# Nixie_Clock_v1_0.net
KiCad netlist of a schematic drawn in EAGLE
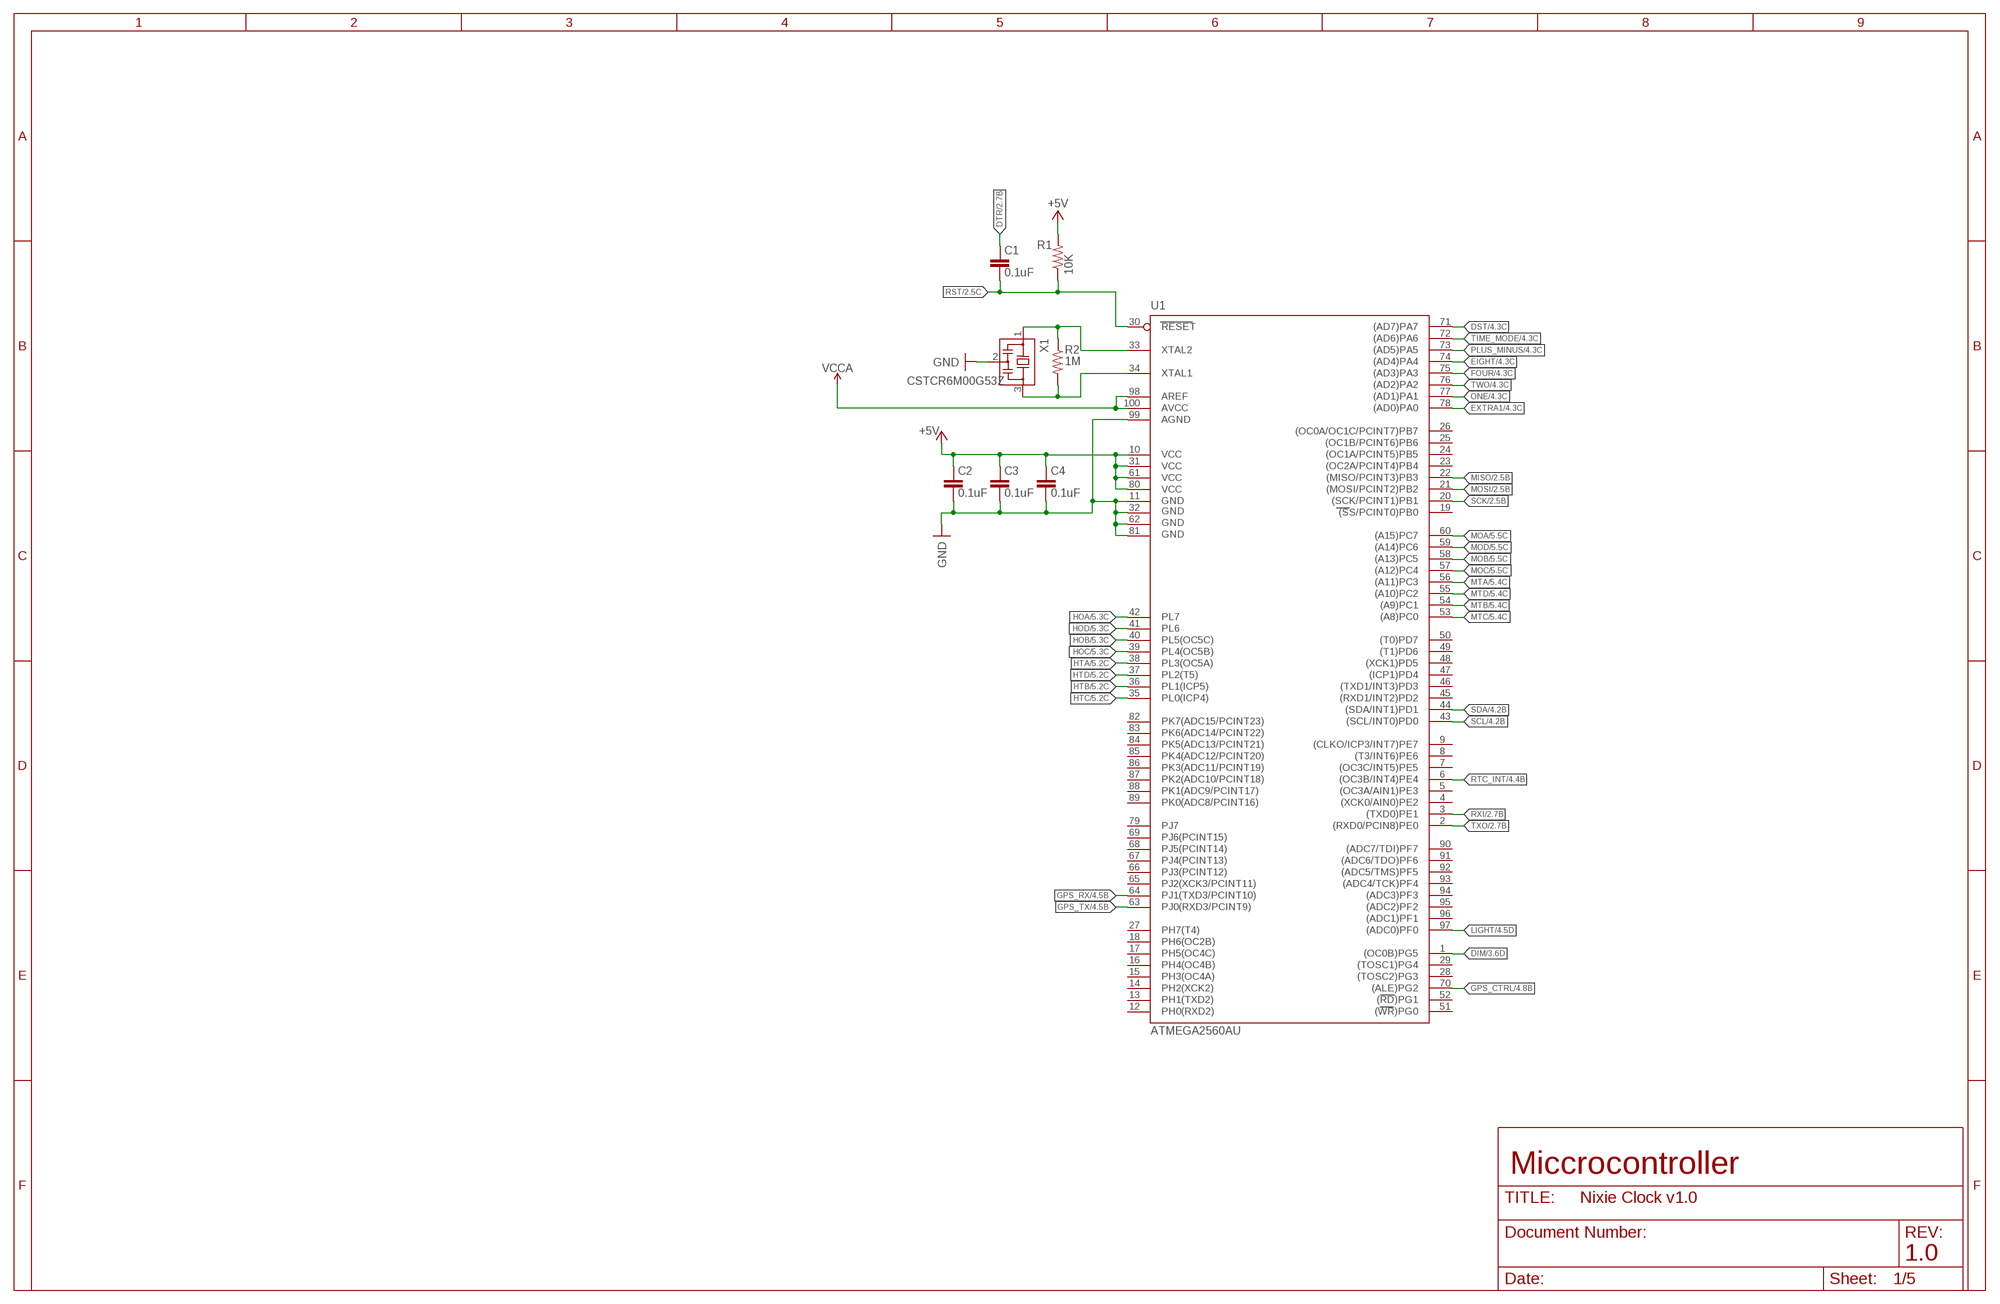
[diagram p0: schematic, sheet 1]
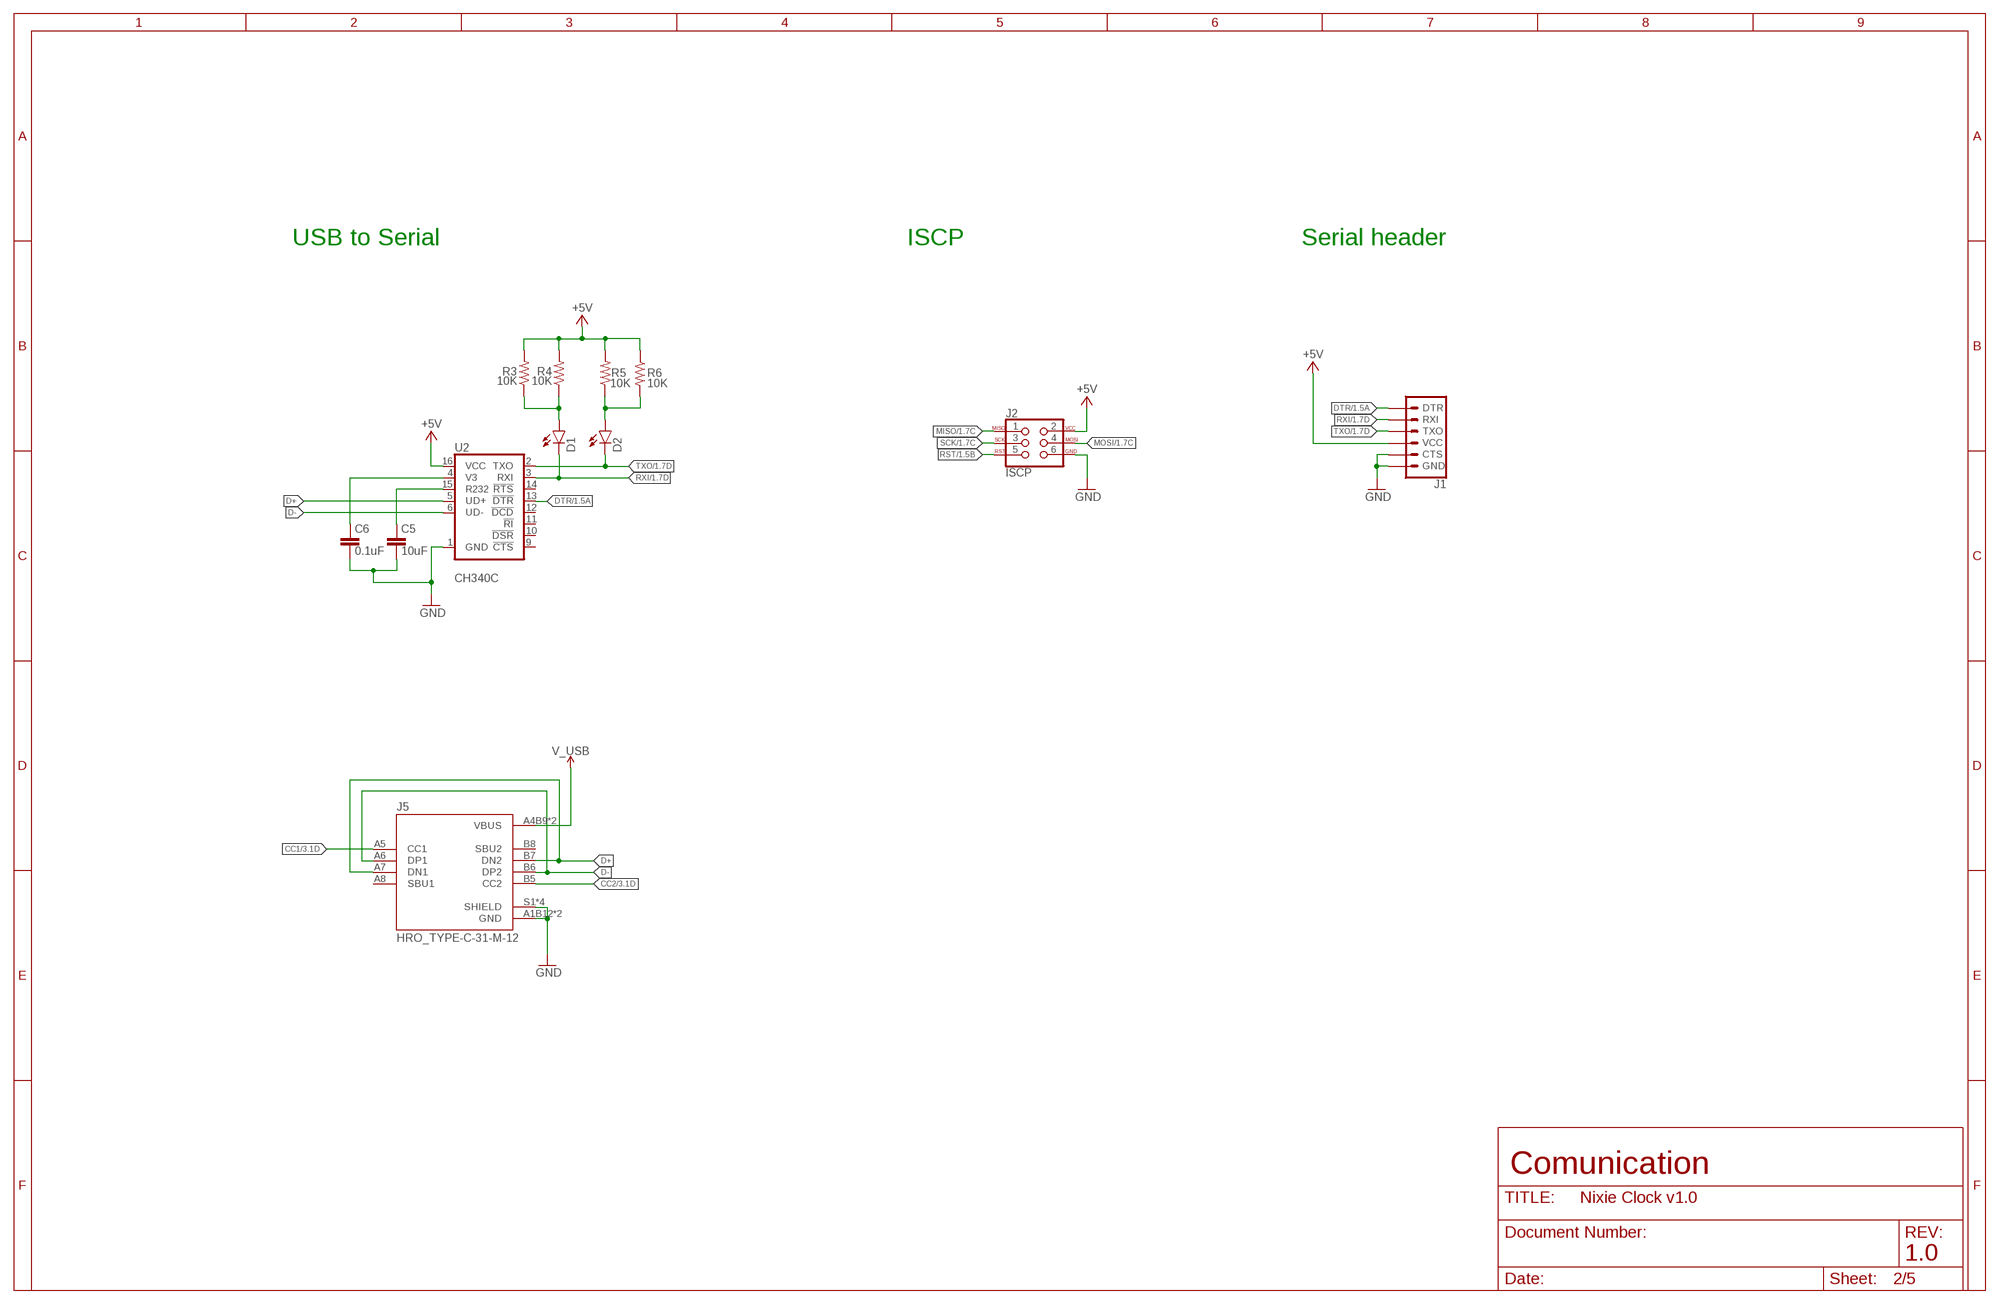
[diagram p1: schematic, sheet 2]
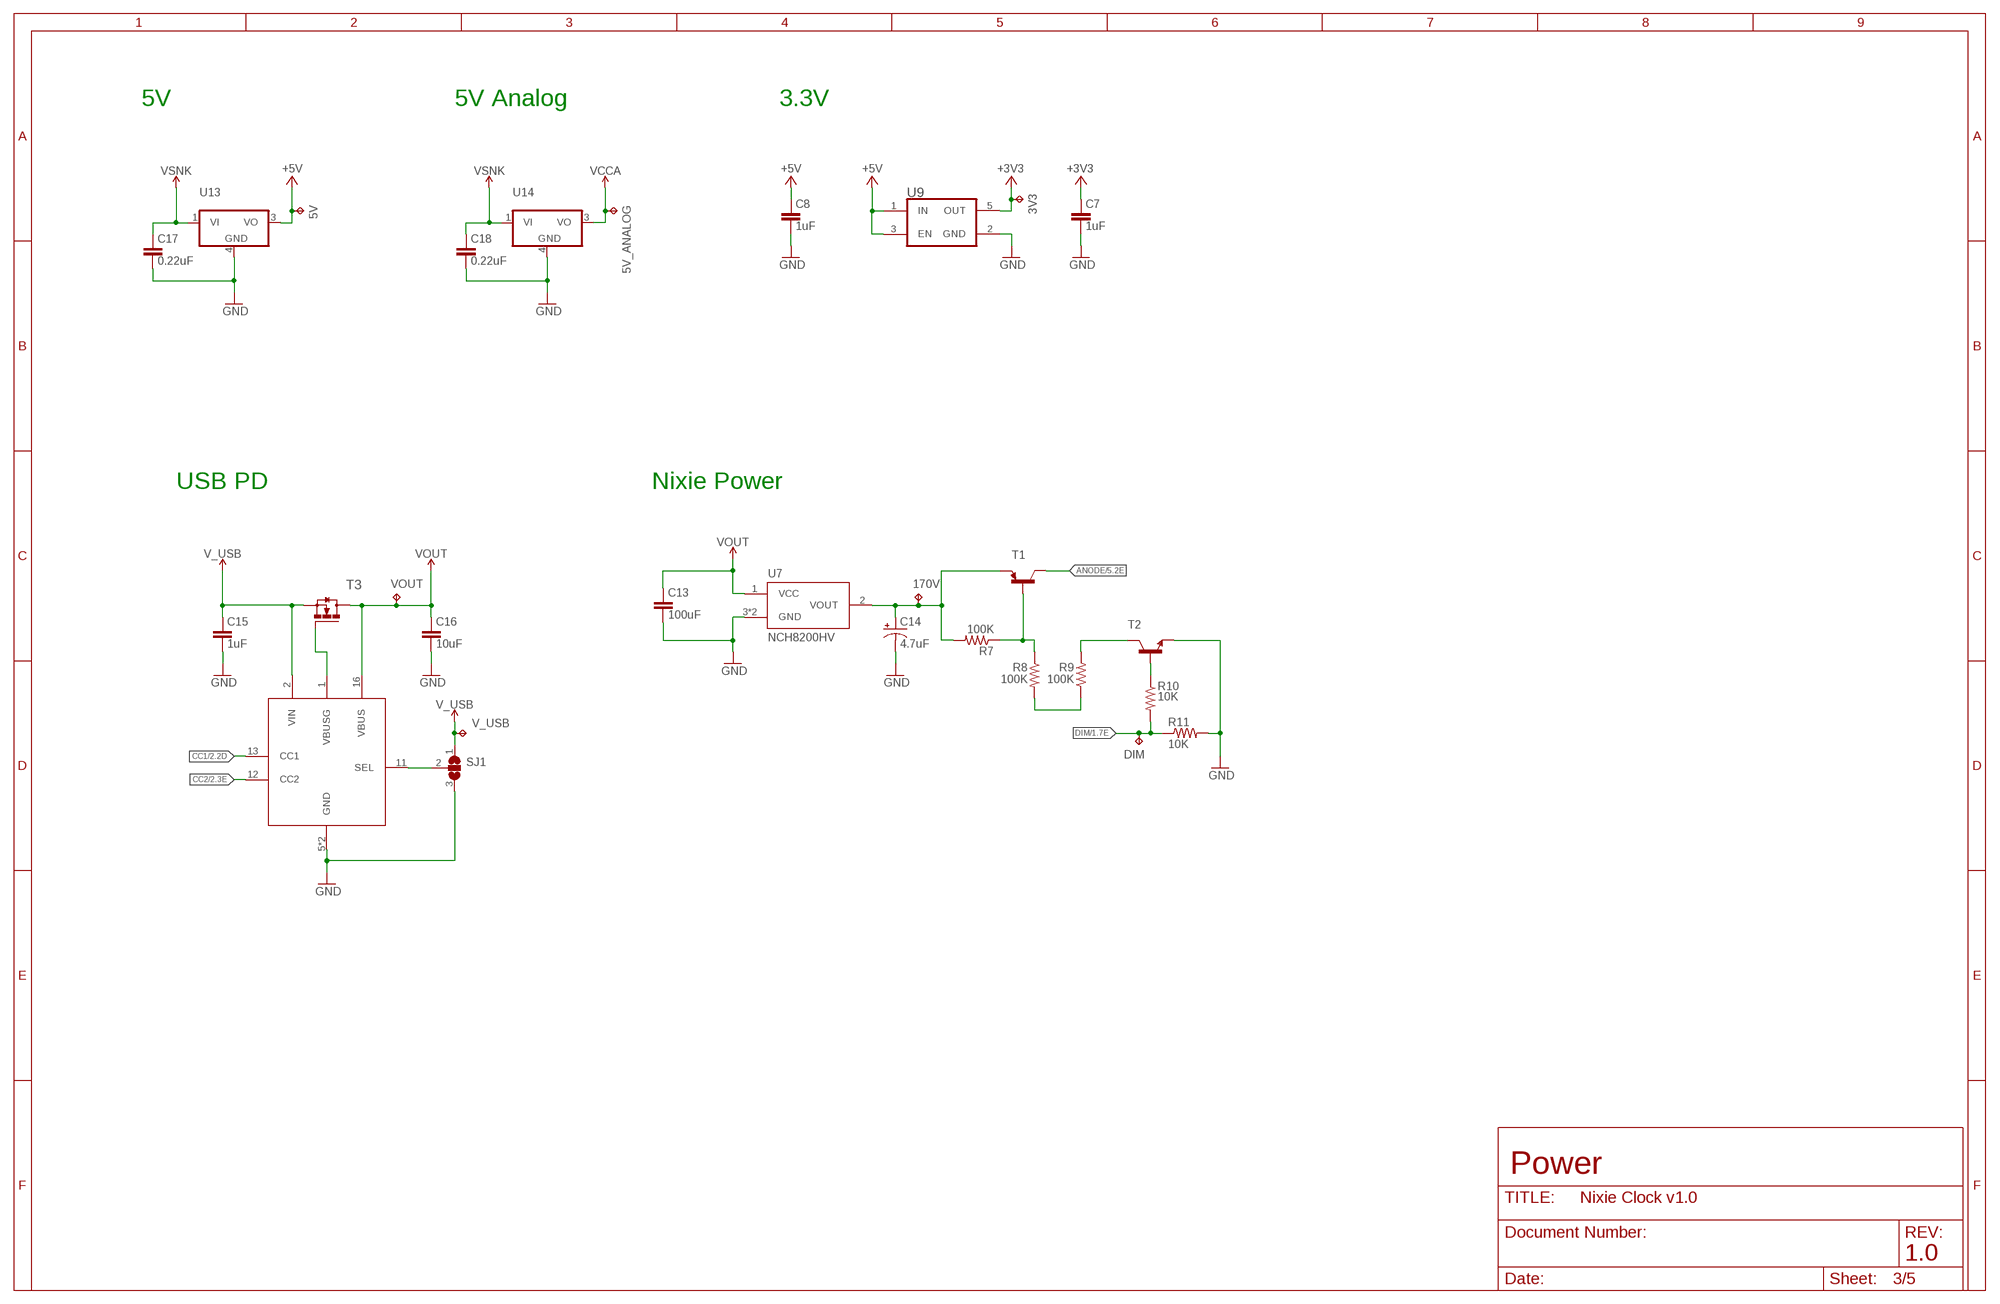
[diagram p2: schematic, sheet 3]
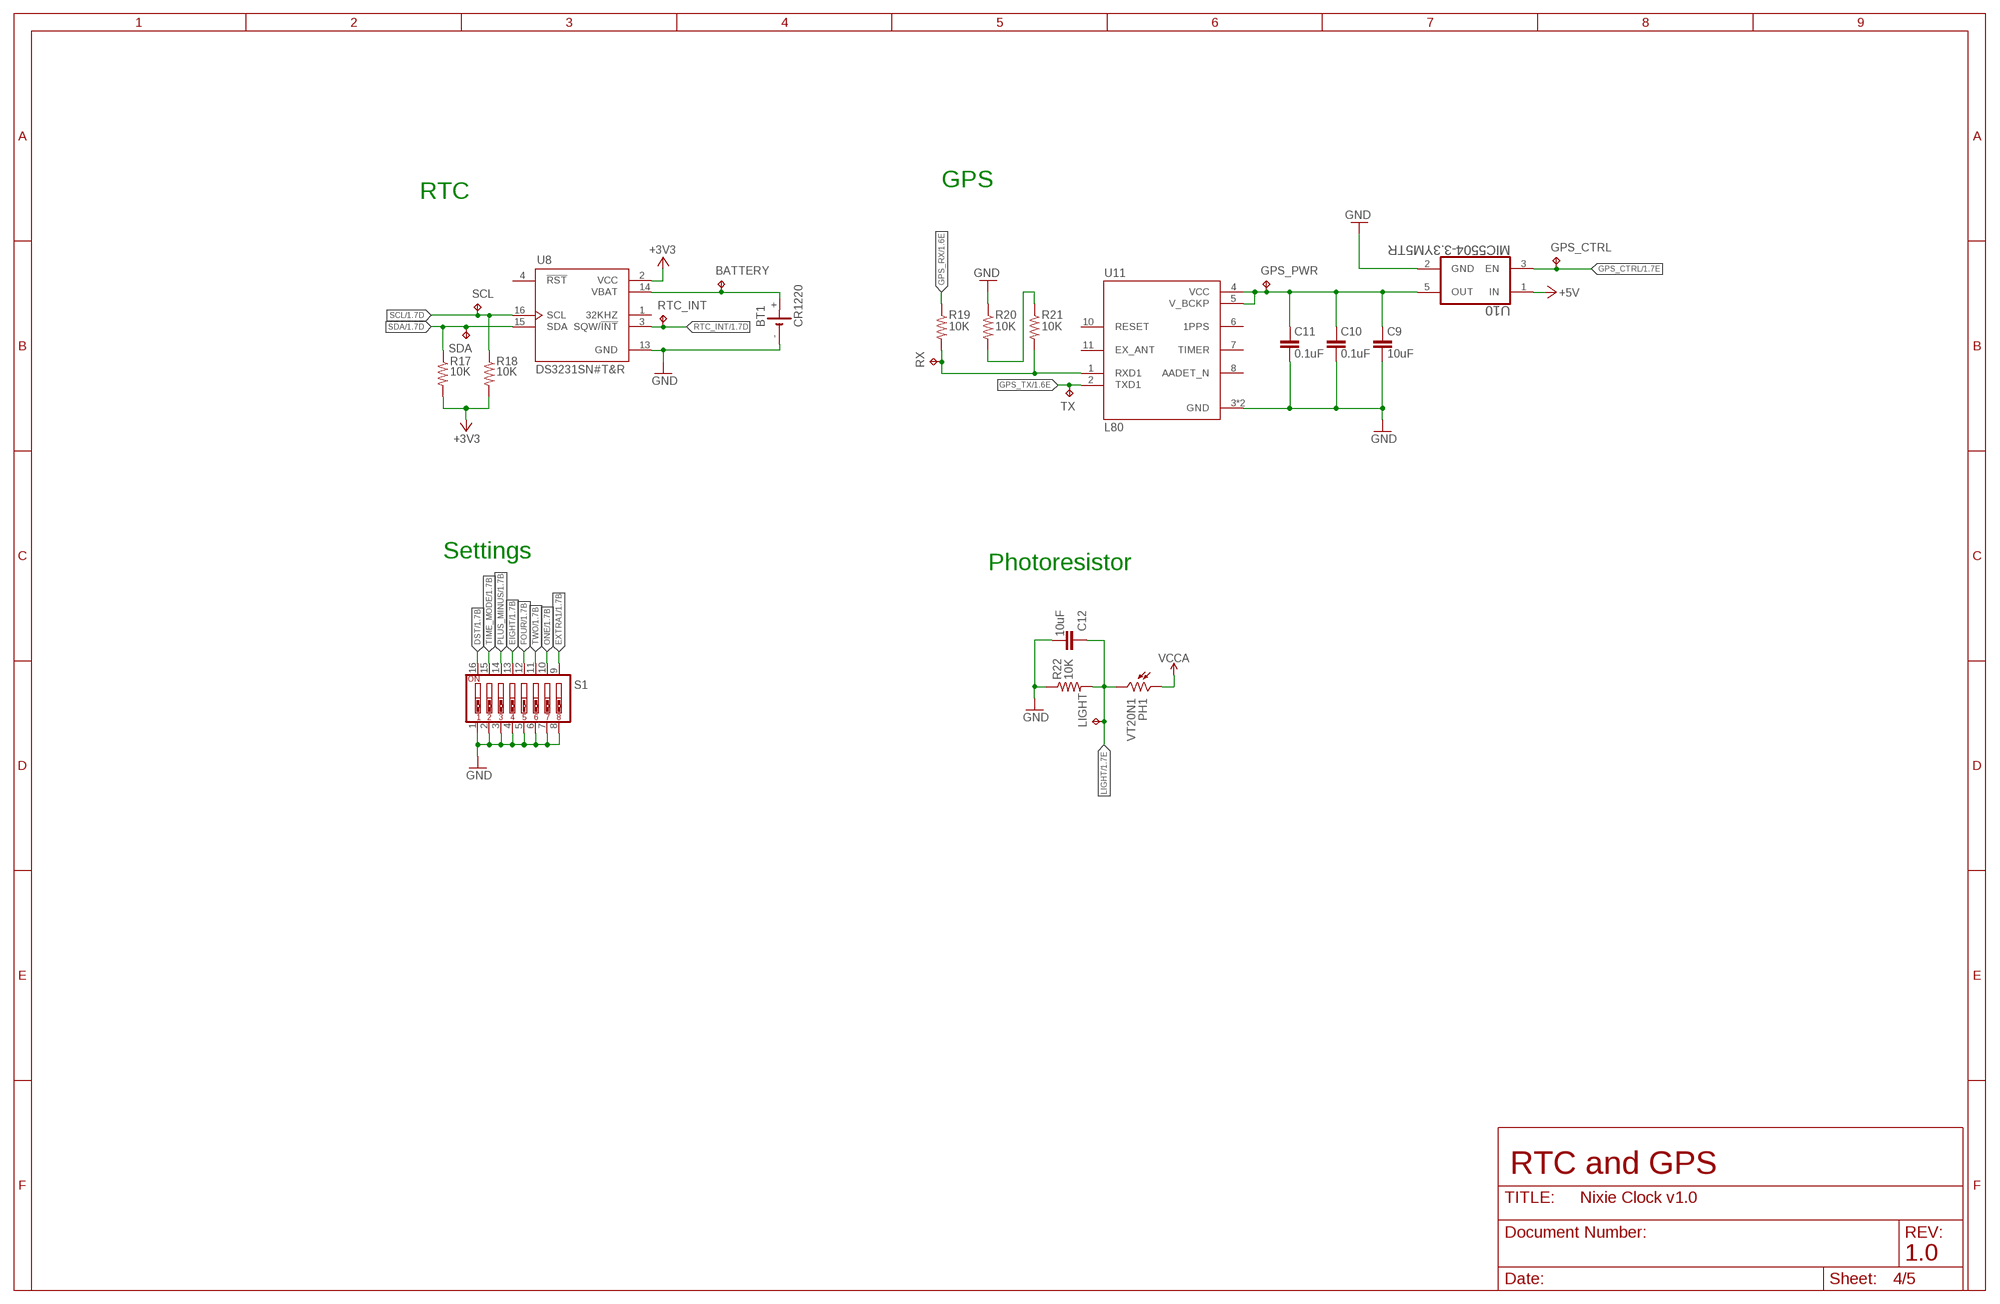
[diagram p3: schematic, sheet 4]
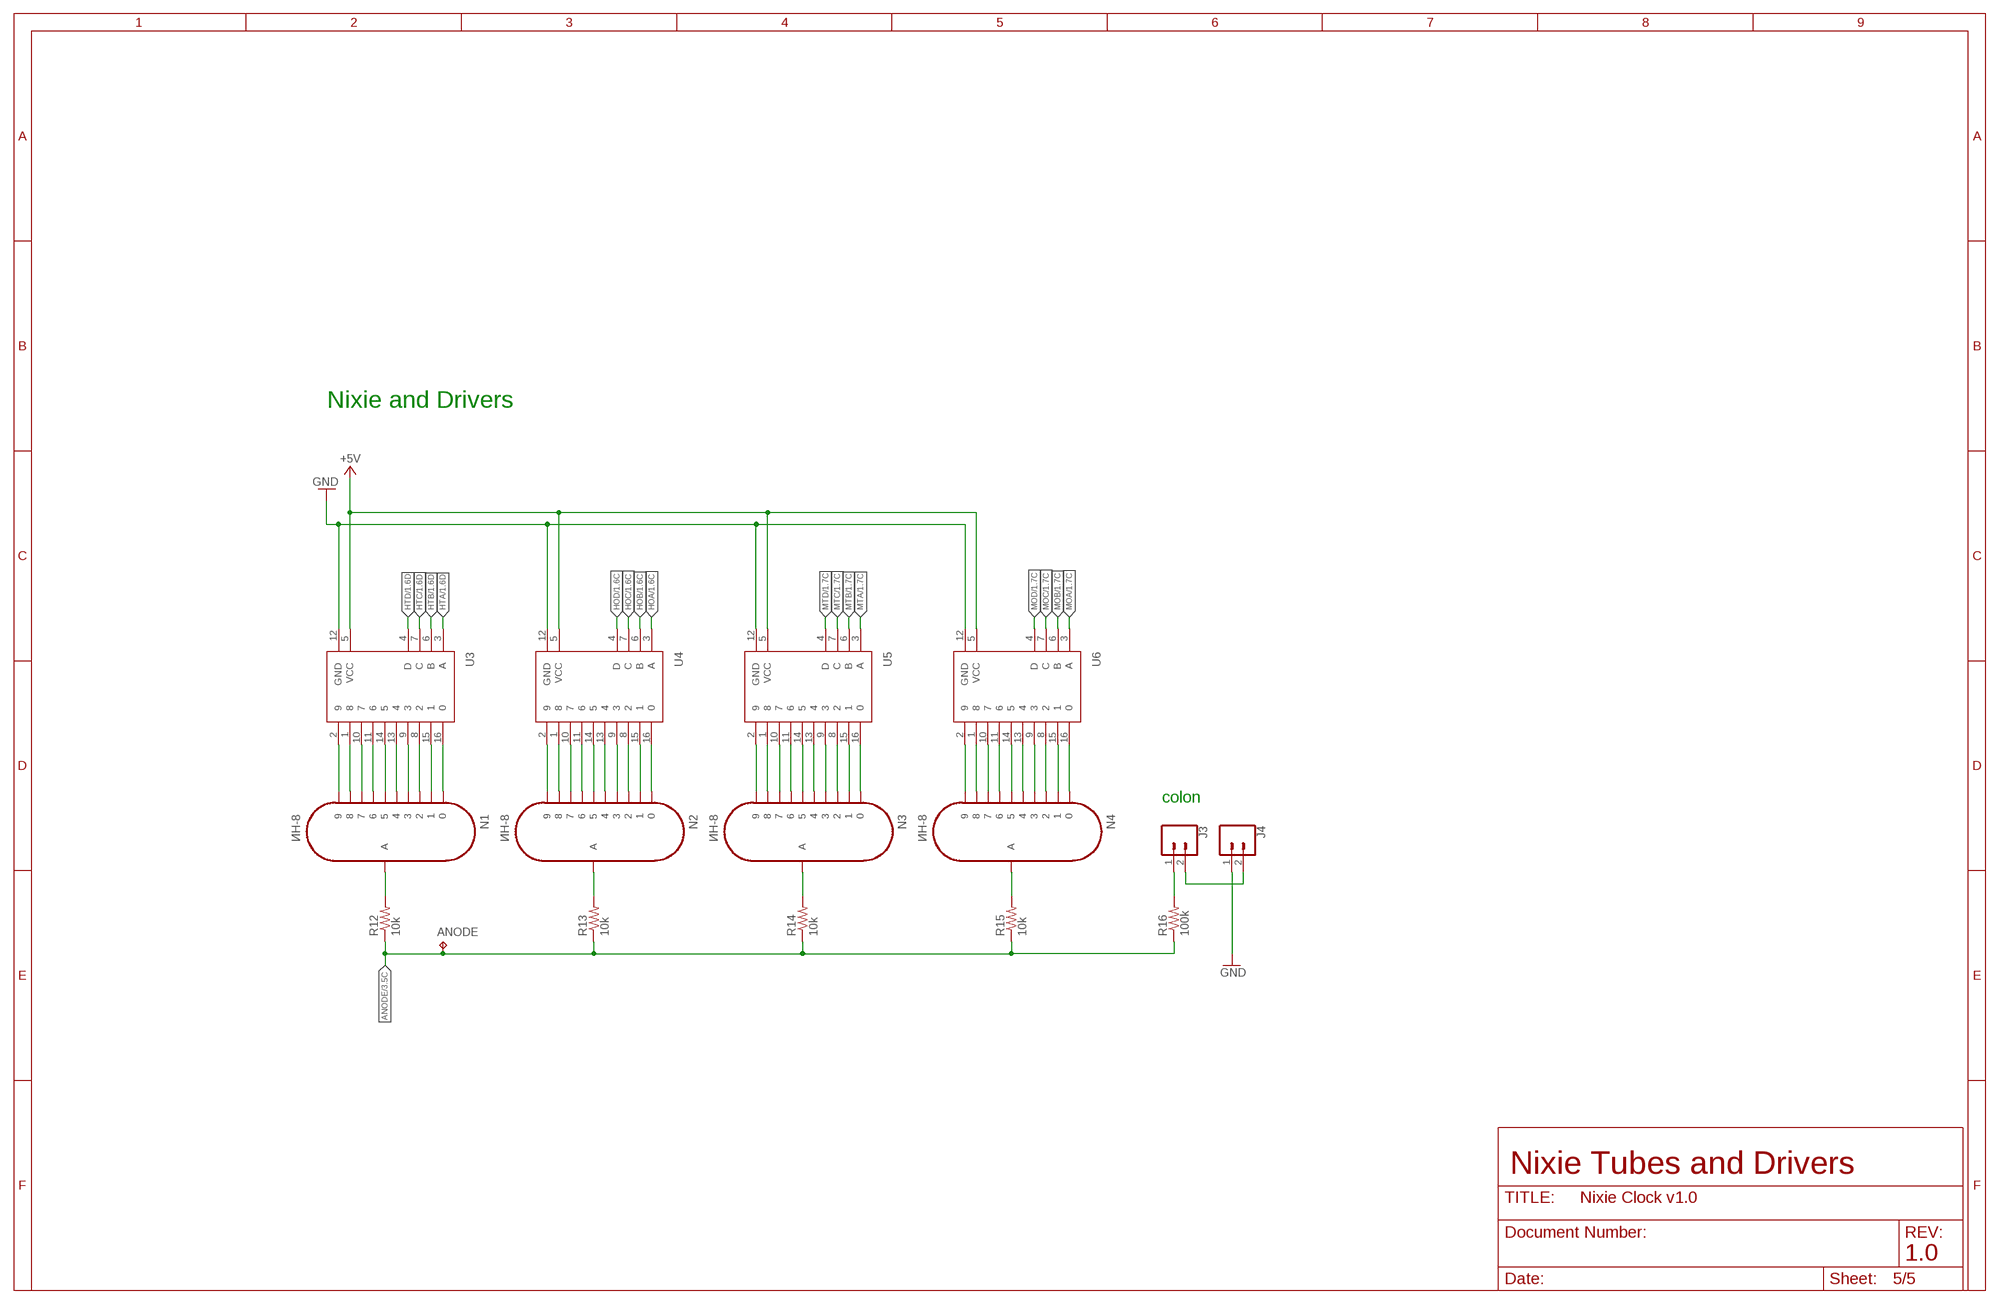
[diagram p4: schematic, sheet 5]

(export (version "E")
  (design (tool "Eeschema 10.0.6"))
  (components
    (comp (ref "C5")
      (value "10uF")
      (footprint "eagle-import:C0603")
      (libsource (lib "eagle-import") (part "C-EUC0603"))
    )
    (comp (ref "C6")
      (value "0.1uF")
      (footprint "eagle-import:C0603")
      (libsource (lib "eagle-import") (part "C-EUC0603"))
    )
    (comp (ref "D1")
      (value "LEDCHIP-LED0603")
      (footprint "eagle-import:CHIP-LED0603")
      (libsource (lib "eagle-import") (part "LEDCHIP-LED0603"))
    )
    (comp (ref "D2")
      (value "LEDCHIP-LED0603")
      (footprint "eagle-import:CHIP-LED0603")
      (libsource (lib "eagle-import") (part "LEDCHIP-LED0603"))
    )
    (comp (ref "J1")
      (value "6_PIN_SERIAL_TARGETSILK")
      (footprint "eagle-import:6_PIN_SERIAL_TARGET_SIDE_W_SILK")
      (libsource (lib "eagle-import") (part "6_PIN_SERIAL_TARGETSILK"))
    )
    (comp (ref "J2")
      (value "ISCP")
      (footprint "eagle-import:2X3")
      (libsource (lib "eagle-import") (part "AVR_SPI_PROG_3X2PTH"))
    )
    (comp (ref "J5")
      (value "HRO_TYPE-C-31-M-12")
      (footprint "eagle-import:HRO_TYPE-C-31-M-12")
      (fields (field (name "MF") "HRO Electronics Co., Ltd.") (field (name "MP") "TYPE-C-31-M-12"))
      (libsource (lib "eagle-import") (part "HRO_TYPE-C-31-M-12"))
    )
    (comp (ref "R3")
      (value "10K")
      (footprint "eagle-import:R0603")
      (libsource (lib "eagle-import") (part "R-US_R0603"))
    )
    (comp (ref "R4")
      (value "10K")
      (footprint "eagle-import:R0603")
      (libsource (lib "eagle-import") (part "R-US_R0603"))
    )
    (comp (ref "R5")
      (value "10K")
      (footprint "eagle-import:R0603")
      (libsource (lib "eagle-import") (part "R-US_R0603"))
    )
    (comp (ref "R6")
      (value "10K")
      (footprint "eagle-import:R0603")
      (libsource (lib "eagle-import") (part "R-US_R0603"))
    )
    (comp (ref "U2")
      (value "CH340C")
      (footprint "eagle-import:SO016")
      (libsource (lib "eagle-import") (part "CH340C"))
    )
    (comp (ref "3V3")
      (value "TPPAD1-13")
      (footprint "eagle-import:P1-13")
      (libsource (lib "eagle-import") (part "TPPAD1-13"))
    )
    (comp (ref "5V")
      (value "TPPAD1-13")
      (footprint "eagle-import:P1-13")
      (libsource (lib "eagle-import") (part "TPPAD1-13"))
    )
    (comp (ref "5V_ANALOG")
      (value "TPPAD1-13")
      (footprint "eagle-import:P1-13")
      (libsource (lib "eagle-import") (part "TPPAD1-13"))
    )
    (comp (ref "170V")
      (value "TPPAD1-13")
      (footprint "eagle-import:P1-13")
      (libsource (lib "eagle-import") (part "TPPAD1-13"))
    )
    (comp (ref "C7")
      (value "1uF")
      (footprint "eagle-import:C0603")
      (libsource (lib "eagle-import") (part "C-EUC0603"))
    )
    (comp (ref "C8")
      (value "1uF")
      (footprint "eagle-import:C0603")
      (libsource (lib "eagle-import") (part "C-EUC0603"))
    )
    (comp (ref "C13")
      (value "100uF")
      (footprint "eagle-import:C0603")
      (libsource (lib "eagle-import") (part "C-EUC0603"))
    )
    (comp (ref "C14")
      (value "4.7uF")
      (footprint "eagle-import:E3,5-8")
      (libsource (lib "eagle-import") (part "CPOL-USE3.5-8"))
    )
    (comp (ref "C15")
      (value "1uF")
      (footprint "eagle-import:C0603")
      (libsource (lib "eagle-import") (part "C-EUC0603"))
    )
    (comp (ref "C16")
      (value "10uF")
      (footprint "eagle-import:C0603")
      (libsource (lib "eagle-import") (part "C-EUC0603"))
    )
    (comp (ref "C17")
      (value "0.22uF")
      (footprint "eagle-import:C0603")
      (libsource (lib "eagle-import") (part "C-EUC0603"))
    )
    (comp (ref "C18")
      (value "0.22uF")
      (footprint "eagle-import:C0603")
      (libsource (lib "eagle-import") (part "C-EUC0603"))
    )
    (comp (ref "DIM")
      (value "TPPAD1-13")
      (footprint "eagle-import:P1-13")
      (libsource (lib "eagle-import") (part "TPPAD1-13"))
    )
    (comp (ref "R7")
      (value "100K")
      (footprint "eagle-import:R0603")
      (libsource (lib "eagle-import") (part "R-US_R0603"))
    )
    (comp (ref "R8")
      (value "100K")
      (footprint "eagle-import:R0603")
      (libsource (lib "eagle-import") (part "R-US_R0603"))
    )
    (comp (ref "R9")
      (value "100K")
      (footprint "eagle-import:R0603")
      (libsource (lib "eagle-import") (part "R-US_R0603"))
    )
    (comp (ref "R10")
      (value "10K")
      (footprint "eagle-import:R0603")
      (libsource (lib "eagle-import") (part "R-US_R0603"))
    )
    (comp (ref "R11")
      (value "10K")
      (footprint "eagle-import:R0603")
      (libsource (lib "eagle-import") (part "R-US_R0603"))
    )
    (comp (ref "SJ1")
      (value "SJ2W")
      (footprint "eagle-import:SJ_2")
      (libsource (lib "eagle-import") (part "SJ2W"))
    )
    (comp (ref "T1")
      (value "PZTA92")
      (footprint "eagle-import:SOT223")
      (libsource (lib "eagle-import") (part "PZTA92"))
    )
    (comp (ref "T2")
      (value "PZTA42")
      (footprint "eagle-import:SOT223")
      (libsource (lib "eagle-import") (part "PZTA42"))
    )
    (comp (ref "T3")
      (value "CSD18543Q3A")
      (footprint "eagle-import:VSONP-8")
      (fields (field (name "MFR") "TI"))
      (libsource (lib "eagle-import") (part "CSD18543Q3A"))
    )
    (comp (ref "U7")
      (value "NCH8200HV")
      (footprint "eagle-import:NCH8200HV")
      (libsource (lib "eagle-import") (part "NCH8200HV"))
    )
    (comp (ref "U9")
      (value "MIC5504-3.3YM5TR")
      (footprint "eagle-import:SOT95P280X130-5N")
      (fields (field (name "MPN") "MIC5504-3.3YM5-TR"))
      (libsource (lib "eagle-import") (part "MIC5504-3.3YM5TR"))
    )
    (comp (ref "U12")
      (value "IP2721")
      (footprint "eagle-import:TSSOP16EXP")
      (libsource (lib "eagle-import") (part "IP2721"))
    )
    (comp (ref "U13")
      (value "LM340MP-05")
      (footprint "eagle-import:SOT223")
      (fields (field (name "MFR") "TI") (field (name "MPN") "LM340MP-5.0/NOPB"))
      (libsource (lib "eagle-import") (part "LM340?-MP05"))
    )
    (comp (ref "U14")
      (value "LM340MP-05")
      (footprint "eagle-import:SOT223")
      (libsource (lib "eagle-import") (part "LM340?-MP05"))
    )
    (comp (ref "VOUT")
      (value "TPPAD1-13")
      (footprint "eagle-import:P1-13")
      (libsource (lib "eagle-import") (part "TPPAD1-13"))
    )
    (comp (ref "V_USB")
      (value "TPPAD1-13")
      (footprint "eagle-import:P1-13")
      (libsource (lib "eagle-import") (part "TPPAD1-13"))
    )
    (comp (ref "C1")
      (value "0.1uF")
      (footprint "eagle-import:C0603")
      (libsource (lib "eagle-import") (part "C-EUC0603"))
    )
    (comp (ref "C2")
      (value "0.1uF")
      (footprint "eagle-import:C0603")
      (libsource (lib "eagle-import") (part "C-EUC0603"))
    )
    (comp (ref "C3")
      (value "0.1uF")
      (footprint "eagle-import:C0603")
      (libsource (lib "eagle-import") (part "C-EUC0603"))
    )
    (comp (ref "C4")
      (value "0.1uF")
      (footprint "eagle-import:C0603")
      (libsource (lib "eagle-import") (part "C-EUC0603"))
    )
    (comp (ref "R1")
      (value "10K")
      (footprint "eagle-import:R0603")
      (libsource (lib "eagle-import") (part "R-US_R0603"))
    )
    (comp (ref "R2")
      (value "1M")
      (footprint "eagle-import:R0603")
      (libsource (lib "eagle-import") (part "R-US_R0603"))
    )
    (comp (ref "U1")
      (value "ATMEGA2560AU")
      (footprint "eagle-import:TQFP100")
      (fields (field (name "MPN") "ATMEGA2560-16AU"))
      (libsource (lib "eagle-import") (part "ATMEGA2560AU"))
    )
    (comp (ref "X1")
      (value "CSTCR6M00G53Z")
      (footprint "eagle-import:CSTCR6M")
      (fields (field (name "MPN") "CSTCR6M00G53-R0") (field (name "MPN_1") "CSTCE16M0V13C99-R0"))
      (libsource (lib "eagle-import") (part "CSTCR6M00G53Z"))
    )
    (comp (ref "ANODE")
      (value "TPPAD1-13")
      (footprint "eagle-import:P1-13")
      (libsource (lib "eagle-import") (part "TPPAD1-13"))
    )
    (comp (ref "J3")
      (value "CONN_02LOCK_LONGPADS")
      (footprint "eagle-import:1X02_LOCK_LONGPADS")
      (libsource (lib "eagle-import") (part "CONN_02LOCK_LONGPADS"))
    )
    (comp (ref "J4")
      (value "CONN_02LOCK_LONGPADS")
      (footprint "eagle-import:1X02_LOCK_LONGPADS")
      (libsource (lib "eagle-import") (part "CONN_02LOCK_LONGPADS"))
    )
    (comp (ref "N1")
      (value "ИН-8")
      (footprint "eagle-import:IN-8_SOCKET")
      (libsource (lib "eagle-import") (part "IN-8IN-8_SOCKET"))
    )
    (comp (ref "N2")
      (value "ИН-8")
      (footprint "eagle-import:IN-8_SOCKET")
      (libsource (lib "eagle-import") (part "IN-8IN-8_SOCKET"))
    )
    (comp (ref "N3")
      (value "ИН-8")
      (footprint "eagle-import:IN-8_SOCKET")
      (libsource (lib "eagle-import") (part "IN-8IN-8_SOCKET"))
    )
    (comp (ref "N4")
      (value "ИН-8")
      (footprint "eagle-import:IN-8_SOCKET")
      (libsource (lib "eagle-import") (part "IN-8IN-8_SOCKET"))
    )
    (comp (ref "R12")
      (value "10k")
      (footprint "eagle-import:M0805")
      (libsource (lib "eagle-import") (part "R-US_M0805"))
    )
    (comp (ref "R13")
      (value "10k")
      (footprint "eagle-import:M0805")
      (libsource (lib "eagle-import") (part "R-US_M0805"))
    )
    (comp (ref "R14")
      (value "10k")
      (footprint "eagle-import:M0805")
      (libsource (lib "eagle-import") (part "R-US_M0805"))
    )
    (comp (ref "R15")
      (value "10k")
      (footprint "eagle-import:M0805")
      (libsource (lib "eagle-import") (part "R-US_M0805"))
    )
    (comp (ref "R16")
      (value "100k")
      (footprint "eagle-import:R0603")
      (libsource (lib "eagle-import") (part "R-US_R0603"))
    )
    (comp (ref "U3")
      (value "K155ID1")
      (footprint "eagle-import:DIL16-KIT")
      (libsource (lib "eagle-import") (part "K155ID1"))
    )
    (comp (ref "U4")
      (value "K155ID1")
      (footprint "eagle-import:DIL16-KIT")
      (libsource (lib "eagle-import") (part "K155ID1"))
    )
    (comp (ref "U5")
      (value "K155ID1")
      (footprint "eagle-import:DIL16-KIT")
      (libsource (lib "eagle-import") (part "K155ID1"))
    )
    (comp (ref "U6")
      (value "K155ID1")
      (footprint "eagle-import:DIL16-KIT")
      (libsource (lib "eagle-import") (part "K155ID1"))
    )
    (comp (ref "BATTERY")
      (value "TPPAD1-13")
      (footprint "eagle-import:P1-13")
      (libsource (lib "eagle-import") (part "TPPAD1-13"))
    )
    (comp (ref "BT1")
      (value "CR1220")
      (footprint "eagle-import:CH291-1220LF")
      (libsource (lib "eagle-import") (part "CH291-1220LF"))
    )
    (comp (ref "C9")
      (value "10uF")
      (footprint "eagle-import:C0603")
      (libsource (lib "eagle-import") (part "C-EUC0603"))
    )
    (comp (ref "C10")
      (value "0.1uF")
      (footprint "eagle-import:C0603")
      (libsource (lib "eagle-import") (part "C-EUC0603"))
    )
    (comp (ref "C11")
      (value "0.1uF")
      (footprint "eagle-import:C0603")
      (libsource (lib "eagle-import") (part "C-EUC0603"))
    )
    (comp (ref "C12")
      (value "10uF")
      (footprint "eagle-import:C0603")
      (libsource (lib "eagle-import") (part "C-EUC0603"))
    )
    (comp (ref "GPS_CTRL")
      (value "TPPAD1-13")
      (footprint "eagle-import:P1-13")
      (libsource (lib "eagle-import") (part "TPPAD1-13"))
    )
    (comp (ref "GPS_PWR")
      (value "TPPAD1-13")
      (footprint "eagle-import:P1-13")
      (libsource (lib "eagle-import") (part "TPPAD1-13"))
    )
    (comp (ref "LIGHT")
      (value "TPPAD1-13")
      (footprint "eagle-import:P1-13")
      (libsource (lib "eagle-import") (part "TPPAD1-13"))
    )
    (comp (ref "PH1")
      (value "VT20N1")
      (footprint "eagle-import:TO46-VT200")
      (libsource (lib "eagle-import") (part "VT20N1"))
    )
    (comp (ref "R17")
      (value "10K")
      (footprint "eagle-import:R0603")
      (libsource (lib "eagle-import") (part "R-US_R0603"))
    )
    (comp (ref "R18")
      (value "10K")
      (footprint "eagle-import:R0603")
      (libsource (lib "eagle-import") (part "R-US_R0603"))
    )
    (comp (ref "R19")
      (value "10K")
      (footprint "eagle-import:R0603")
      (libsource (lib "eagle-import") (part "R-US_R0603"))
    )
    (comp (ref "R20")
      (value "10K")
      (footprint "eagle-import:R0603")
      (libsource (lib "eagle-import") (part "R-US_R0603"))
    )
    (comp (ref "R21")
      (value "10K")
      (footprint "eagle-import:R0603")
      (libsource (lib "eagle-import") (part "R-US_R0603"))
    )
    (comp (ref "R22")
      (value "10K")
      (footprint "eagle-import:R0603")
      (libsource (lib "eagle-import") (part "R-US_R0603"))
    )
    (comp (ref "RTC_INT")
      (value "TPPAD1-13")
      (footprint "eagle-import:P1-13")
      (libsource (lib "eagle-import") (part "TPPAD1-13"))
    )
    (comp (ref "RX")
      (value "TPPAD1-13")
      (footprint "eagle-import:P1-13")
      (libsource (lib "eagle-import") (part "TPPAD1-13"))
    )
    (comp (ref "S1")
      (value "SW_DIP-8")
      (footprint "eagle-import:EDG-08")
      (libsource (lib "eagle-import") (part "SW_DIP-8"))
    )
    (comp (ref "SCL")
      (value "TPPAD1-13")
      (footprint "eagle-import:P1-13")
      (libsource (lib "eagle-import") (part "TPPAD1-13"))
    )
    (comp (ref "SDA")
      (value "TPPAD1-13")
      (footprint "eagle-import:P1-13")
      (libsource (lib "eagle-import") (part "TPPAD1-13"))
    )
    (comp (ref "TX")
      (value "TPPAD1-13")
      (footprint "eagle-import:P1-13")
      (libsource (lib "eagle-import") (part "TPPAD1-13"))
    )
    (comp (ref "U8")
      (value "DS3231SN#T&R")
      (footprint "eagle-import:SOIC127P1032X265-16N")
      (fields (field (name "MF") "Maxim Integrated") (field (name "MP") "DS3231SN#T&amp;R"))
      (libsource (lib "eagle-import") (part "DS3231SN#T&R"))
    )
    (comp (ref "U10")
      (value "MIC5504-3.3YM5TR")
      (footprint "eagle-import:SOT95P280X130-5N")
      (fields (field (name "MPN") "MIC5504-3.3YM5-TR"))
      (libsource (lib "eagle-import") (part "MIC5504-3.3YM5TR"))
    )
    (comp (ref "U11")
      (value "L80")
      (footprint "eagle-import:XCVR_L80")
      (fields (field (name "MF") "Quectel") (field (name "MP") "L80-M39"))
      (libsource (lib "eagle-import") (part "L80"))
    )
  )
  (nets
    (net (code "1") (name "+3V3") (class "Default")
      (node (ref "3V3") (pin "TP") (pinfunction "TP_TP") (pintype "input"))
      (node (ref "C7") (pin "1") (pinfunction "1_1") (pintype "passive"))
      (node (ref "R17") (pin "2") (pinfunction "2_2") (pintype "passive"))
      (node (ref "R18") (pin "2") (pinfunction "2_2") (pintype "passive"))
      (node (ref "U8") (pin "2") (pinfunction "VCC_2") (pintype "power_in"))
      (node (ref "U9") (pin "5") (pinfunction "OUT_5") (pintype "output"))
    )
    (net (code "2") (name "+5V") (class "Default")
      (node (ref "5V") (pin "TP") (pinfunction "TP_TP") (pintype "input"))
      (node (ref "C2") (pin "1") (pinfunction "1_1") (pintype "passive"))
      (node (ref "C3") (pin "1") (pinfunction "1_1") (pintype "passive"))
      (node (ref "C4") (pin "1") (pinfunction "1_1") (pintype "passive"))
      (node (ref "C8") (pin "1") (pinfunction "1_1") (pintype "passive"))
      (node (ref "J1") (pin "P$4") (pinfunction "VCC_P$4") (pintype "passive"))
      (node (ref "J2") (pin "2") (pinfunction "2_2") (pintype "passive"))
      (node (ref "R1") (pin "2") (pinfunction "2_2") (pintype "passive"))
      (node (ref "R3") (pin "2") (pinfunction "2_2") (pintype "passive"))
      (node (ref "R4") (pin "2") (pinfunction "2_2") (pintype "passive"))
      (node (ref "R5") (pin "2") (pinfunction "2_2") (pintype "passive"))
      (node (ref "R6") (pin "1") (pinfunction "1_1") (pintype "passive"))
      (node (ref "U1") (pin "10") (pinfunction "VCC_10") (pintype "power_in"))
      (node (ref "U1") (pin "31") (pinfunction "VCC1_31") (pintype "power_in"))
      (node (ref "U1") (pin "61") (pinfunction "VCC2_61") (pintype "power_in"))
      (node (ref "U1") (pin "80") (pinfunction "VCC3_80") (pintype "power_in"))
      (node (ref "U10") (pin "1") (pinfunction "IN_1") (pintype "input"))
      (node (ref "U13") (pin "3") (pinfunction "VO_3") (pintype "passive"))
      (node (ref "U2") (pin "16") (pinfunction "VCC_16") (pintype "bidirectional"))
      (node (ref "U3") (pin "5") (pinfunction "VCC_5") (pintype "bidirectional"))
      (node (ref "U4") (pin "5") (pinfunction "VCC_5") (pintype "bidirectional"))
      (node (ref "U5") (pin "5") (pinfunction "VCC_5") (pintype "bidirectional"))
      (node (ref "U6") (pin "5") (pinfunction "VCC_5") (pintype "bidirectional"))
      (node (ref "U9") (pin "1") (pinfunction "IN_1") (pintype "input"))
      (node (ref "U9") (pin "3") (pinfunction "EN_3") (pintype "input"))
    )
    (net (code "3") (name "ANODE") (class "Default")
      (node (ref "ANODE") (pin "TP") (pinfunction "TP_TP") (pintype "input"))
      (node (ref "R12") (pin "1") (pinfunction "1_1") (pintype "passive"))
      (node (ref "R13") (pin "1") (pinfunction "1_1") (pintype "passive"))
      (node (ref "R14") (pin "1") (pinfunction "1_1") (pintype "passive"))
      (node (ref "R15") (pin "1") (pinfunction "1_1") (pintype "passive"))
      (node (ref "R16") (pin "1") (pinfunction "1_1") (pintype "passive"))
      (node (ref "T1") (pin "2") (pinfunction "C_2") (pintype "passive"))
      (node (ref "T1") (pin "4") (pinfunction "C_4") (pintype "passive"))
    )
    (net (code "4") (name "CC1") (class "Default")
      (node (ref "J5") (pin "A5") (pinfunction "CC1_A5") (pintype "bidirectional"))
      (node (ref "U12") (pin "13") (pinfunction "CC1_13") (pintype "bidirectional"))
    )
    (net (code "5") (name "CC2") (class "Default")
      (node (ref "J5") (pin "B5") (pinfunction "CC2_B5") (pintype "bidirectional"))
      (node (ref "U12") (pin "12") (pinfunction "CC2_12") (pintype "bidirectional"))
    )
    (net (code "6") (name "D+") (class "Default")
      (node (ref "J5") (pin "A7") (pinfunction "DN1_A7") (pintype "bidirectional"))
      (node (ref "J5") (pin "B7") (pinfunction "DN2_B7") (pintype "bidirectional"))
      (node (ref "U2") (pin "5") (pinfunction "UD+_5") (pintype "bidirectional"))
    )
    (net (code "7") (name "D-") (class "Default")
      (node (ref "J5") (pin "A6") (pinfunction "DP1_A6") (pintype "bidirectional"))
      (node (ref "J5") (pin "B6") (pinfunction "DP2_B6") (pintype "bidirectional"))
      (node (ref "U2") (pin "6") (pinfunction "UD-_6") (pintype "bidirectional"))
    )
    (net (code "8") (name "DIM") (class "Default")
      (node (ref "DIM") (pin "TP") (pinfunction "TP_TP") (pintype "input"))
      (node (ref "R10") (pin "2") (pinfunction "2_2") (pintype "passive"))
      (node (ref "R11") (pin "1") (pinfunction "1_1") (pintype "passive"))
      (node (ref "U1") (pin "1") (pinfunction "(OC0B)PG5_1") (pintype "bidirectional"))
    )
    (net (code "9") (name "DST") (class "Default")
      (node (ref "S1") (pin "16") (pinfunction "16_16") (pintype "passive"))
      (node (ref "U1") (pin "71") (pinfunction "(AD7)PA7_71") (pintype "bidirectional"))
    )
    (net (code "10") (name "DTR") (class "Default")
      (node (ref "C1") (pin "1") (pinfunction "1_1") (pintype "passive"))
      (node (ref "J1") (pin "P$1") (pinfunction "DTR_P$1") (pintype "passive"))
      (node (ref "U2") (pin "13") (pinfunction "~{DTR}_13") (pintype "bidirectional"))
    )
    (net (code "11") (name "EIGHT") (class "Default")
      (node (ref "S1") (pin "13") (pinfunction "13_13") (pintype "passive"))
      (node (ref "U1") (pin "74") (pinfunction "(AD4)PA4_74") (pintype "bidirectional"))
    )
    (net (code "12") (name "EXTRA1") (class "Default")
      (node (ref "S1") (pin "9") (pinfunction "9_9") (pintype "passive"))
      (node (ref "U1") (pin "78") (pinfunction "(AD0)PA0_78") (pintype "bidirectional"))
    )
    (net (code "13") (name "FOUR") (class "Default")
      (node (ref "S1") (pin "12") (pinfunction "12_12") (pintype "passive"))
      (node (ref "U1") (pin "75") (pinfunction "(AD3)PA3_75") (pintype "bidirectional"))
    )
    (net (code "14") (name "GND") (class "Default")
      (node (ref "BT1") (pin "-") (pinfunction "-_-") (pintype "passive"))
      (node (ref "C10") (pin "2") (pinfunction "2_2") (pintype "passive"))
      (node (ref "C11") (pin "2") (pinfunction "2_2") (pintype "passive"))
      (node (ref "C12") (pin "2") (pinfunction "2_2") (pintype "passive"))
      (node (ref "C13") (pin "2") (pinfunction "2_2") (pintype "passive"))
      (node (ref "C14") (pin "-") (pinfunction "-_-") (pintype "passive"))
      (node (ref "C15") (pin "2") (pinfunction "2_2") (pintype "passive"))
      (node (ref "C16") (pin "2") (pinfunction "2_2") (pintype "passive"))
      (node (ref "C17") (pin "2") (pinfunction "2_2") (pintype "passive"))
      (node (ref "C18") (pin "2") (pinfunction "2_2") (pintype "passive"))
      (node (ref "C2") (pin "2") (pinfunction "2_2") (pintype "passive"))
      (node (ref "C3") (pin "2") (pinfunction "2_2") (pintype "passive"))
      (node (ref "C4") (pin "2") (pinfunction "2_2") (pintype "passive"))
      (node (ref "C5") (pin "2") (pinfunction "2_2") (pintype "passive"))
      (node (ref "C6") (pin "2") (pinfunction "2_2") (pintype "passive"))
      (node (ref "C7") (pin "2") (pinfunction "2_2") (pintype "passive"))
      (node (ref "C8") (pin "2") (pinfunction "2_2") (pintype "passive"))
      (node (ref "C9") (pin "2") (pinfunction "2_2") (pintype "passive"))
      (node (ref "J1") (pin "P$5") (pinfunction "CTS_P$5") (pintype "passive"))
      (node (ref "J1") (pin "P$6") (pinfunction "GND_P$6") (pintype "passive"))
      (node (ref "J2") (pin "6") (pinfunction "6_6") (pintype "passive"))
      (node (ref "J4") (pin "1") (pinfunction "1_1") (pintype "passive"))
      (node (ref "J5") (pin "A1B12") (pinfunction "GND_A1B12") (pintype "power_in"))
      (node (ref "J5") (pin "B1A12") (pinfunction "GND_B1A12") (pintype "power_in"))
      (node (ref "J5") (pin "S1") (pinfunction "SHIELD_S1") (pintype "passive"))
      (node (ref "J5") (pin "S2") (pinfunction "SHIELD_S2") (pintype "passive"))
      (node (ref "J5") (pin "S3") (pinfunction "SHIELD_S3") (pintype "passive"))
      (node (ref "J5") (pin "S4") (pinfunction "SHIELD_S4") (pintype "passive"))
      (node (ref "R11") (pin "2") (pinfunction "2_2") (pintype "passive"))
      (node (ref "R20") (pin "1") (pinfunction "1_1") (pintype "passive"))
      (node (ref "R22") (pin "1") (pinfunction "1_1") (pintype "passive"))
      (node (ref "S1") (pin "1") (pinfunction "1_1") (pintype "passive"))
      (node (ref "S1") (pin "2") (pinfunction "2_2") (pintype "passive"))
      (node (ref "S1") (pin "3") (pinfunction "3_3") (pintype "passive"))
      (node (ref "S1") (pin "4") (pinfunction "4_4") (pintype "passive"))
      (node (ref "S1") (pin "5") (pinfunction "5_5") (pintype "passive"))
      (node (ref "S1") (pin "6") (pinfunction "6_6") (pintype "passive"))
      (node (ref "S1") (pin "7") (pinfunction "7_7") (pintype "passive"))
      (node (ref "S1") (pin "8") (pinfunction "8_8") (pintype "passive"))
      (node (ref "SJ1") (pin "3") (pinfunction "3_3") (pintype "passive"))
      (node (ref "T2") (pin "3") (pinfunction "E_3") (pintype "passive"))
      (node (ref "U1") (pin "11") (pinfunction "GND_11") (pintype "power_in"))
      (node (ref "U1") (pin "32") (pinfunction "GND1_32") (pintype "power_in"))
      (node (ref "U1") (pin "62") (pinfunction "GND2_62") (pintype "power_in"))
      (node (ref "U1") (pin "81") (pinfunction "GND3_81") (pintype "power_in"))
      (node (ref "U1") (pin "99") (pinfunction "AGND_99") (pintype "power_in"))
      (node (ref "U10") (pin "2") (pinfunction "GND_2") (pintype "passive"))
      (node (ref "U11") (pin "12") (pinfunction "GND_12") (pintype "power_in"))
      (node (ref "U11") (pin "3") (pinfunction "GND_3") (pintype "power_in"))
      (node (ref "U12") (pin "5") (pinfunction "GND_5") (pintype "bidirectional"))
      (node (ref "U12") (pin "EXP") (pinfunction "GND_EXP") (pintype "bidirectional"))
      (node (ref "U13") (pin "4") (pinfunction "GND_4") (pintype "passive"))
      (node (ref "U14") (pin "4") (pinfunction "GND_4") (pintype "passive"))
      (node (ref "U2") (pin "1") (pinfunction "GND_1") (pintype "bidirectional"))
      (node (ref "U3") (pin "12") (pinfunction "GND_12") (pintype "bidirectional"))
      (node (ref "U4") (pin "12") (pinfunction "GND_12") (pintype "bidirectional"))
      (node (ref "U5") (pin "12") (pinfunction "GND_12") (pintype "bidirectional"))
      (node (ref "U6") (pin "12") (pinfunction "GND_12") (pintype "bidirectional"))
      (node (ref "U7") (pin "3") (pinfunction "GND_3") (pintype "bidirectional"))
      (node (ref "U7") (pin "4") (pinfunction "GND_4") (pintype "bidirectional"))
      (node (ref "U8") (pin "13") (pinfunction "GND_13") (pintype "power_in"))
      (node (ref "U9") (pin "2") (pinfunction "GND_2") (pintype "passive"))
      (node (ref "X1") (pin "2") (pinfunction "2_2") (pintype "passive"))
    )
    (net (code "15") (name "GPS_CTRL") (class "Default")
      (node (ref "GPS_CTRL") (pin "TP") (pinfunction "TP_TP") (pintype "input"))
      (node (ref "U1") (pin "70") (pinfunction "(ALE)PG2_70") (pintype "bidirectional"))
      (node (ref "U10") (pin "3") (pinfunction "EN_3") (pintype "input"))
    )
    (net (code "16") (name "GPS_RX") (class "Default")
      (node (ref "R19") (pin "1") (pinfunction "1_1") (pintype "passive"))
      (node (ref "U1") (pin "64") (pinfunction "PJ1(TXD3/PCINT10)_64") (pintype "bidirectional"))
    )
    (net (code "17") (name "GPS_TX") (class "Default")
      (node (ref "TX") (pin "TP") (pinfunction "TP_TP") (pintype "input"))
      (node (ref "U1") (pin "63") (pinfunction "PJ0(RXD3/PCINT9)_63") (pintype "bidirectional"))
      (node (ref "U11") (pin "2") (pinfunction "TXD1_2") (pintype "output"))
    )
    (net (code "18") (name "HOA") (class "Default")
      (node (ref "U1") (pin "42") (pinfunction "PL7_42") (pintype "bidirectional"))
      (node (ref "U4") (pin "3") (pinfunction "A_3") (pintype "input"))
    )
    (net (code "19") (name "HOB") (class "Default")
      (node (ref "U1") (pin "40") (pinfunction "PL5(OC5C)_40") (pintype "bidirectional"))
      (node (ref "U4") (pin "6") (pinfunction "B_6") (pintype "input"))
    )
    (net (code "20") (name "HOC") (class "Default")
      (node (ref "U1") (pin "39") (pinfunction "PL4(OC5B)_39") (pintype "bidirectional"))
      (node (ref "U4") (pin "7") (pinfunction "C_7") (pintype "input"))
    )
    (net (code "21") (name "HOD") (class "Default")
      (node (ref "U1") (pin "41") (pinfunction "PL6_41") (pintype "bidirectional"))
      (node (ref "U4") (pin "4") (pinfunction "D_4") (pintype "input"))
    )
    (net (code "22") (name "HTA") (class "Default")
      (node (ref "U1") (pin "38") (pinfunction "PL3(OC5A)_38") (pintype "bidirectional"))
      (node (ref "U3") (pin "3") (pinfunction "A_3") (pintype "input"))
    )
    (net (code "23") (name "HTB") (class "Default")
      (node (ref "U1") (pin "36") (pinfunction "PL1(ICP5)_36") (pintype "bidirectional"))
      (node (ref "U3") (pin "6") (pinfunction "B_6") (pintype "input"))
    )
    (net (code "24") (name "HTC") (class "Default")
      (node (ref "U1") (pin "35") (pinfunction "PL0(ICP4)_35") (pintype "bidirectional"))
      (node (ref "U3") (pin "7") (pinfunction "C_7") (pintype "input"))
    )
    (net (code "25") (name "HTD") (class "Default")
      (node (ref "U1") (pin "37") (pinfunction "PL2(T5)_37") (pintype "bidirectional"))
      (node (ref "U3") (pin "4") (pinfunction "D_4") (pintype "input"))
    )
    (net (code "26") (name "LIGHT") (class "Default")
      (node (ref "C12") (pin "1") (pinfunction "1_1") (pintype "passive"))
      (node (ref "LIGHT") (pin "TP") (pinfunction "TP_TP") (pintype "input"))
      (node (ref "PH1") (pin "2") (pinfunction "2_2") (pintype "passive"))
      (node (ref "R22") (pin "2") (pinfunction "2_2") (pintype "passive"))
      (node (ref "U1") (pin "97") (pinfunction "(ADC0)PF0_97") (pintype "bidirectional"))
    )
    (net (code "27") (name "MISO") (class "Default")
      (node (ref "J2") (pin "1") (pinfunction "1_1") (pintype "passive"))
      (node (ref "U1") (pin "22") (pinfunction "(MISO/PCINT3)PB3_22") (pintype "bidirectional"))
    )
    (net (code "28") (name "MOA") (class "Default")
      (node (ref "U1") (pin "60") (pinfunction "(A15)PC7_60") (pintype "bidirectional"))
      (node (ref "U6") (pin "3") (pinfunction "A_3") (pintype "input"))
    )
    (net (code "29") (name "MOB") (class "Default")
      (node (ref "U1") (pin "58") (pinfunction "(A13)PC5_58") (pintype "bidirectional"))
      (node (ref "U6") (pin "6") (pinfunction "B_6") (pintype "input"))
    )
    (net (code "30") (name "MOC") (class "Default")
      (node (ref "U1") (pin "57") (pinfunction "(A12)PC4_57") (pintype "bidirectional"))
      (node (ref "U6") (pin "7") (pinfunction "C_7") (pintype "input"))
    )
    (net (code "31") (name "MOD") (class "Default")
      (node (ref "U1") (pin "59") (pinfunction "(A14)PC6_59") (pintype "bidirectional"))
      (node (ref "U6") (pin "4") (pinfunction "D_4") (pintype "input"))
    )
    (net (code "32") (name "MOSI") (class "Default")
      (node (ref "J2") (pin "4") (pinfunction "4_4") (pintype "passive"))
      (node (ref "U1") (pin "21") (pinfunction "(MOSI/PCINT2)PB2_21") (pintype "bidirectional"))
    )
    (net (code "33") (name "MTA") (class "Default")
      (node (ref "U1") (pin "56") (pinfunction "(A11)PC3_56") (pintype "bidirectional"))
      (node (ref "U5") (pin "3") (pinfunction "A_3") (pintype "input"))
    )
    (net (code "34") (name "MTB") (class "Default")
      (node (ref "U1") (pin "54") (pinfunction "(A9)PC1_54") (pintype "bidirectional"))
      (node (ref "U5") (pin "6") (pinfunction "B_6") (pintype "input"))
    )
    (net (code "35") (name "MTC") (class "Default")
      (node (ref "U1") (pin "53") (pinfunction "(A8)PC0_53") (pintype "bidirectional"))
      (node (ref "U5") (pin "7") (pinfunction "C_7") (pintype "input"))
    )
    (net (code "36") (name "MTD") (class "Default")
      (node (ref "U1") (pin "55") (pinfunction "(A10)PC2_55") (pintype "bidirectional"))
      (node (ref "U5") (pin "4") (pinfunction "D_4") (pintype "input"))
    )
    (net (code "37") (name "Net-(D1-PadA)") (class "Default")
      (node (ref "D1") (pin "A") (pinfunction "A_A") (pintype "passive"))
      (node (ref "R3") (pin "1") (pinfunction "1_1") (pintype "passive"))
      (node (ref "R4") (pin "1") (pinfunction "1_1") (pintype "passive"))
    )
    (net (code "38") (name "Net-(D2-PadA)") (class "Default")
      (node (ref "D2") (pin "A") (pinfunction "A_A") (pintype "passive"))
      (node (ref "R5") (pin "1") (pinfunction "1_1") (pintype "passive"))
      (node (ref "R6") (pin "2") (pinfunction "2_2") (pintype "passive"))
    )
    (net (code "39") (name "Net-(J3-Pad1)") (class "Default")
      (node (ref "J3") (pin "1") (pinfunction "1_1") (pintype "passive"))
      (node (ref "R16") (pin "2") (pinfunction "2_2") (pintype "passive"))
    )
    (net (code "40") (name "Net-(J3-Pad2)") (class "Default")
      (node (ref "J3") (pin "2") (pinfunction "2_2") (pintype "passive"))
      (node (ref "J4") (pin "2") (pinfunction "2_2") (pintype "passive"))
    )
    (net (code "41") (name "Net-(N1-PadA)") (class "Default")
      (node (ref "N1") (pin "A") (pinfunction "A_A") (pintype "bidirectional"))
      (node (ref "R12") (pin "2") (pinfunction "2_2") (pintype "passive"))
    )
    (net (code "42") (name "Net-(N2-PadA)") (class "Default")
      (node (ref "N2") (pin "A") (pinfunction "A_A") (pintype "bidirectional"))
      (node (ref "R13") (pin "2") (pinfunction "2_2") (pintype "passive"))
    )
    (net (code "43") (name "Net-(N3-PadA)") (class "Default")
      (node (ref "N3") (pin "A") (pinfunction "A_A") (pintype "bidirectional"))
      (node (ref "R14") (pin "2") (pinfunction "2_2") (pintype "passive"))
    )
    (net (code "44") (name "Net-(N4-PadA)") (class "Default")
      (node (ref "N4") (pin "A") (pinfunction "A_A") (pintype "bidirectional"))
      (node (ref "R15") (pin "2") (pinfunction "2_2") (pintype "passive"))
    )
    (net (code "45") (name "Net-(R8-Pad2)") (class "Default")
      (node (ref "R8") (pin "2") (pinfunction "2_2") (pintype "passive"))
      (node (ref "R9") (pin "1") (pinfunction "1_1") (pintype "passive"))
    )
    (net (code "46") (name "Net-(R9-Pad2)") (class "Default")
      (node (ref "R9") (pin "2") (pinfunction "2_2") (pintype "passive"))
      (node (ref "T2") (pin "2") (pinfunction "C_2") (pintype "passive"))
      (node (ref "T2") (pin "4") (pinfunction "C_4") (pintype "passive"))
    )
    (net (code "47") (name "Net-(R20-Pad2)") (class "Default")
      (node (ref "R20") (pin "2") (pinfunction "2_2") (pintype "passive"))
      (node (ref "R21") (pin "1") (pinfunction "1_1") (pintype "passive"))
    )
    (net (code "48") (name "Net-(T1-B)") (class "Default")
      (node (ref "R7") (pin "1") (pinfunction "1_1") (pintype "passive"))
      (node (ref "R8") (pin "1") (pinfunction "1_1") (pintype "passive"))
      (node (ref "T1") (pin "1") (pinfunction "B_1") (pintype "passive"))
    )
    (net (code "49") (name "Net-(T1-E)") (class "Default")
      (node (ref "170V") (pin "TP") (pinfunction "TP_TP") (pintype "input"))
      (node (ref "C14") (pin "+") (pinfunction "+_+") (pintype "passive"))
      (node (ref "R7") (pin "2") (pinfunction "2_2") (pintype "passive"))
      (node (ref "T1") (pin "3") (pinfunction "E_3") (pintype "passive"))
      (node (ref "U7") (pin "2") (pinfunction "VOUT_2") (pintype "bidirectional"))
    )
    (net (code "50") (name "Net-(T2-B)") (class "Default")
      (node (ref "R10") (pin "1") (pinfunction "1_1") (pintype "passive"))
      (node (ref "T2") (pin "1") (pinfunction "B_1") (pintype "passive"))
    )
    (net (code "51") (name "Net-(T3-G)") (class "Default")
      (node (ref "T3") (pin "4") (pinfunction "G_4") (pintype "passive"))
      (node (ref "U12") (pin "1") (pinfunction "VBUSG_1") (pintype "bidirectional"))
    )
    (net (code "52") (name "Net-(U1-XTAL1)") (class "Default")
      (node (ref "R2") (pin "2") (pinfunction "2_2") (pintype "passive"))
      (node (ref "U1") (pin "34") (pinfunction "XTAL1_34") (pintype "input"))
      (node (ref "X1") (pin "3") (pinfunction "3_3") (pintype "passive"))
    )
    (net (code "53") (name "Net-(U1-XTAL2)") (class "Default")
      (node (ref "R2") (pin "1") (pinfunction "1_1") (pintype "passive"))
      (node (ref "U1") (pin "33") (pinfunction "XTAL2_33") (pintype "output"))
      (node (ref "X1") (pin "1") (pinfunction "1_1") (pintype "passive"))
    )
    (net (code "54") (name "Net-(U2-R232)") (class "Default")
      (node (ref "C5") (pin "1") (pinfunction "1_1") (pintype "passive"))
      (node (ref "U2") (pin "15") (pinfunction "R232_15") (pintype "bidirectional"))
    )
    (net (code "55") (name "Net-(U2-V3)") (class "Default")
      (node (ref "C6") (pin "1") (pinfunction "1_1") (pintype "passive"))
      (node (ref "U2") (pin "4") (pinfunction "V3_4") (pintype "bidirectional"))
    )
    (net (code "56") (name "Net-(U3-0)") (class "Default")
      (node (ref "N1") (pin "0") (pinfunction "0_0") (pintype "bidirectional"))
      (node (ref "U3") (pin "16") (pinfunction "0_16") (pintype "bidirectional"))
    )
    (net (code "57") (name "Net-(U3-1)") (class "Default")
      (node (ref "N1") (pin "1") (pinfunction "1_1") (pintype "bidirectional"))
      (node (ref "U3") (pin "15") (pinfunction "1_15") (pintype "bidirectional"))
    )
    (net (code "58") (name "Net-(U3-2)") (class "Default")
      (node (ref "N1") (pin "2") (pinfunction "2_2") (pintype "bidirectional"))
      (node (ref "U3") (pin "8") (pinfunction "2_8") (pintype "bidirectional"))
    )
    (net (code "59") (name "Net-(U3-3)") (class "Default")
      (node (ref "N1") (pin "3") (pinfunction "3_3") (pintype "bidirectional"))
      (node (ref "U3") (pin "9") (pinfunction "3_9") (pintype "bidirectional"))
    )
    (net (code "60") (name "Net-(U3-4)") (class "Default")
      (node (ref "N1") (pin "4") (pinfunction "4_4") (pintype "bidirectional"))
      (node (ref "U3") (pin "13") (pinfunction "4_13") (pintype "bidirectional"))
    )
    (net (code "61") (name "Net-(U3-5)") (class "Default")
      (node (ref "N1") (pin "5") (pinfunction "5_5") (pintype "bidirectional"))
      (node (ref "U3") (pin "14") (pinfunction "5_14") (pintype "bidirectional"))
    )
    (net (code "62") (name "Net-(U3-6)") (class "Default")
      (node (ref "N1") (pin "6") (pinfunction "6_6") (pintype "bidirectional"))
      (node (ref "U3") (pin "11") (pinfunction "6_11") (pintype "bidirectional"))
    )
    (net (code "63") (name "Net-(U3-7)") (class "Default")
      (node (ref "N1") (pin "7") (pinfunction "7_7") (pintype "bidirectional"))
      (node (ref "U3") (pin "10") (pinfunction "7_10") (pintype "bidirectional"))
    )
    (net (code "64") (name "Net-(U3-8)") (class "Default")
      (node (ref "N1") (pin "8") (pinfunction "8_8") (pintype "bidirectional"))
      (node (ref "U3") (pin "1") (pinfunction "8_1") (pintype "bidirectional"))
    )
    (net (code "65") (name "Net-(U3-9)") (class "Default")
      (node (ref "N1") (pin "9") (pinfunction "9_9") (pintype "bidirectional"))
      (node (ref "U3") (pin "2") (pinfunction "9_2") (pintype "bidirectional"))
    )
    (net (code "66") (name "Net-(U4-0)") (class "Default")
      (node (ref "N2") (pin "0") (pinfunction "0_0") (pintype "bidirectional"))
      (node (ref "U4") (pin "16") (pinfunction "0_16") (pintype "bidirectional"))
    )
    (net (code "67") (name "Net-(U4-1)") (class "Default")
      (node (ref "N2") (pin "1") (pinfunction "1_1") (pintype "bidirectional"))
      (node (ref "U4") (pin "15") (pinfunction "1_15") (pintype "bidirectional"))
    )
    (net (code "68") (name "Net-(U4-2)") (class "Default")
      (node (ref "N2") (pin "2") (pinfunction "2_2") (pintype "bidirectional"))
      (node (ref "U4") (pin "8") (pinfunction "2_8") (pintype "bidirectional"))
    )
    (net (code "69") (name "Net-(U4-3)") (class "Default")
      (node (ref "N2") (pin "3") (pinfunction "3_3") (pintype "bidirectional"))
      (node (ref "U4") (pin "9") (pinfunction "3_9") (pintype "bidirectional"))
    )
    (net (code "70") (name "Net-(U4-4)") (class "Default")
      (node (ref "N2") (pin "4") (pinfunction "4_4") (pintype "bidirectional"))
      (node (ref "U4") (pin "13") (pinfunction "4_13") (pintype "bidirectional"))
    )
    (net (code "71") (name "Net-(U4-5)") (class "Default")
      (node (ref "N2") (pin "5") (pinfunction "5_5") (pintype "bidirectional"))
      (node (ref "U4") (pin "14") (pinfunction "5_14") (pintype "bidirectional"))
    )
    (net (code "72") (name "Net-(U4-6)") (class "Default")
      (node (ref "N2") (pin "6") (pinfunction "6_6") (pintype "bidirectional"))
      (node (ref "U4") (pin "11") (pinfunction "6_11") (pintype "bidirectional"))
    )
    (net (code "73") (name "Net-(U4-7)") (class "Default")
      (node (ref "N2") (pin "7") (pinfunction "7_7") (pintype "bidirectional"))
      (node (ref "U4") (pin "10") (pinfunction "7_10") (pintype "bidirectional"))
    )
    (net (code "74") (name "Net-(U4-8)") (class "Default")
      (node (ref "N2") (pin "8") (pinfunction "8_8") (pintype "bidirectional"))
      (node (ref "U4") (pin "1") (pinfunction "8_1") (pintype "bidirectional"))
    )
    (net (code "75") (name "Net-(U4-9)") (class "Default")
      (node (ref "N2") (pin "9") (pinfunction "9_9") (pintype "bidirectional"))
      (node (ref "U4") (pin "2") (pinfunction "9_2") (pintype "bidirectional"))
    )
    (net (code "76") (name "Net-(U5-0)") (class "Default")
      (node (ref "N3") (pin "0") (pinfunction "0_0") (pintype "bidirectional"))
      (node (ref "U5") (pin "16") (pinfunction "0_16") (pintype "bidirectional"))
    )
    (net (code "77") (name "Net-(U5-1)") (class "Default")
      (node (ref "N3") (pin "1") (pinfunction "1_1") (pintype "bidirectional"))
      (node (ref "U5") (pin "15") (pinfunction "1_15") (pintype "bidirectional"))
    )
    (net (code "78") (name "Net-(U5-2)") (class "Default")
      (node (ref "N3") (pin "2") (pinfunction "2_2") (pintype "bidirectional"))
      (node (ref "U5") (pin "8") (pinfunction "2_8") (pintype "bidirectional"))
    )
    (net (code "79") (name "Net-(U5-3)") (class "Default")
      (node (ref "N3") (pin "3") (pinfunction "3_3") (pintype "bidirectional"))
      (node (ref "U5") (pin "9") (pinfunction "3_9") (pintype "bidirectional"))
    )
    (net (code "80") (name "Net-(U5-4)") (class "Default")
      (node (ref "N3") (pin "4") (pinfunction "4_4") (pintype "bidirectional"))
      (node (ref "U5") (pin "13") (pinfunction "4_13") (pintype "bidirectional"))
    )
    (net (code "81") (name "Net-(U5-5)") (class "Default")
      (node (ref "N3") (pin "5") (pinfunction "5_5") (pintype "bidirectional"))
      (node (ref "U5") (pin "14") (pinfunction "5_14") (pintype "bidirectional"))
    )
    (net (code "82") (name "Net-(U5-6)") (class "Default")
      (node (ref "N3") (pin "6") (pinfunction "6_6") (pintype "bidirectional"))
      (node (ref "U5") (pin "11") (pinfunction "6_11") (pintype "bidirectional"))
    )
    (net (code "83") (name "Net-(U5-7)") (class "Default")
      (node (ref "N3") (pin "7") (pinfunction "7_7") (pintype "bidirectional"))
      (node (ref "U5") (pin "10") (pinfunction "7_10") (pintype "bidirectional"))
    )
    (net (code "84") (name "Net-(U5-8)") (class "Default")
      (node (ref "N3") (pin "8") (pinfunction "8_8") (pintype "bidirectional"))
      (node (ref "U5") (pin "1") (pinfunction "8_1") (pintype "bidirectional"))
    )
    (net (code "85") (name "Net-(U5-9)") (class "Default")
      (node (ref "N3") (pin "9") (pinfunction "9_9") (pintype "bidirectional"))
      (node (ref "U5") (pin "2") (pinfunction "9_2") (pintype "bidirectional"))
    )
    (net (code "86") (name "Net-(U6-0)") (class "Default")
      (node (ref "N4") (pin "0") (pinfunction "0_0") (pintype "bidirectional"))
      (node (ref "U6") (pin "16") (pinfunction "0_16") (pintype "bidirectional"))
    )
    (net (code "87") (name "Net-(U6-1)") (class "Default")
      (node (ref "N4") (pin "1") (pinfunction "1_1") (pintype "bidirectional"))
      (node (ref "U6") (pin "15") (pinfunction "1_15") (pintype "bidirectional"))
    )
    (net (code "88") (name "Net-(U6-2)") (class "Default")
      (node (ref "N4") (pin "2") (pinfunction "2_2") (pintype "bidirectional"))
      (node (ref "U6") (pin "8") (pinfunction "2_8") (pintype "bidirectional"))
    )
    (net (code "89") (name "Net-(U6-3)") (class "Default")
      (node (ref "N4") (pin "3") (pinfunction "3_3") (pintype "bidirectional"))
      (node (ref "U6") (pin "9") (pinfunction "3_9") (pintype "bidirectional"))
    )
    (net (code "90") (name "Net-(U6-4)") (class "Default")
      (node (ref "N4") (pin "4") (pinfunction "4_4") (pintype "bidirectional"))
      (node (ref "U6") (pin "13") (pinfunction "4_13") (pintype "bidirectional"))
    )
    (net (code "91") (name "Net-(U6-5)") (class "Default")
      (node (ref "N4") (pin "5") (pinfunction "5_5") (pintype "bidirectional"))
      (node (ref "U6") (pin "14") (pinfunction "5_14") (pintype "bidirectional"))
    )
    (net (code "92") (name "Net-(U6-6)") (class "Default")
      (node (ref "N4") (pin "6") (pinfunction "6_6") (pintype "bidirectional"))
      (node (ref "U6") (pin "11") (pinfunction "6_11") (pintype "bidirectional"))
    )
    (net (code "93") (name "Net-(U6-7)") (class "Default")
      (node (ref "N4") (pin "7") (pinfunction "7_7") (pintype "bidirectional"))
      (node (ref "U6") (pin "10") (pinfunction "7_10") (pintype "bidirectional"))
    )
    (net (code "94") (name "Net-(U6-8)") (class "Default")
      (node (ref "N4") (pin "8") (pinfunction "8_8") (pintype "bidirectional"))
      (node (ref "U6") (pin "1") (pinfunction "8_1") (pintype "bidirectional"))
    )
    (net (code "95") (name "Net-(U6-9)") (class "Default")
      (node (ref "N4") (pin "9") (pinfunction "9_9") (pintype "bidirectional"))
      (node (ref "U6") (pin "2") (pinfunction "9_2") (pintype "bidirectional"))
    )
    (net (code "96") (name "Net-(U8-VBAT)") (class "Default")
      (node (ref "BATTERY") (pin "TP") (pinfunction "TP_TP") (pintype "input"))
      (node (ref "BT1") (pin "+") (pinfunction "+_+") (pintype "passive"))
      (node (ref "U8") (pin "14") (pinfunction "VBAT_14") (pintype "power_in"))
    )
    (net (code "97") (name "Net-(U10-OUT)") (class "Default")
      (node (ref "C10") (pin "1") (pinfunction "1_1") (pintype "passive"))
      (node (ref "C11") (pin "1") (pinfunction "1_1") (pintype "passive"))
      (node (ref "C9") (pin "1") (pinfunction "1_1") (pintype "passive"))
      (node (ref "GPS_PWR") (pin "TP") (pinfunction "TP_TP") (pintype "input"))
      (node (ref "U10") (pin "5") (pinfunction "OUT_5") (pintype "output"))
      (node (ref "U11") (pin "4") (pinfunction "VCC_4") (pintype "power_in"))
      (node (ref "U11") (pin "5") (pinfunction "V_BCKP_5") (pintype "power_in"))
    )
    (net (code "98") (name "Net-(U11-RXD1)") (class "Default")
      (node (ref "R19") (pin "2") (pinfunction "2_2") (pintype "passive"))
      (node (ref "R21") (pin "2") (pinfunction "2_2") (pintype "passive"))
      (node (ref "RX") (pin "TP") (pinfunction "TP_TP") (pintype "input"))
      (node (ref "U11") (pin "1") (pinfunction "RXD1_1") (pintype "input"))
    )
    (net (code "99") (name "Net-(U12-SEL)") (class "Default")
      (node (ref "SJ1") (pin "2") (pinfunction "2_2") (pintype "passive"))
      (node (ref "U12") (pin "11") (pinfunction "SEL_11") (pintype "bidirectional"))
    )
    (net (code "100") (name "ONE") (class "Default")
      (node (ref "S1") (pin "10") (pinfunction "10_10") (pintype "passive"))
      (node (ref "U1") (pin "77") (pinfunction "(AD1)PA1_77") (pintype "bidirectional"))
    )
    (net (code "101") (name "PLUS_MINUS") (class "Default")
      (node (ref "S1") (pin "14") (pinfunction "14_14") (pintype "passive"))
      (node (ref "U1") (pin "73") (pinfunction "(AD5)PA5_73") (pintype "bidirectional"))
    )
    (net (code "102") (name "RST") (class "Default")
      (node (ref "C1") (pin "2") (pinfunction "2_2") (pintype "passive"))
      (node (ref "J2") (pin "5") (pinfunction "5_5") (pintype "passive"))
      (node (ref "R1") (pin "1") (pinfunction "1_1") (pintype "passive"))
      (node (ref "U1") (pin "30") (pinfunction "RESET_30") (pintype "input"))
    )
    (net (code "103") (name "RTC_INT") (class "Default")
      (node (ref "RTC_INT") (pin "TP") (pinfunction "TP_TP") (pintype "input"))
      (node (ref "U1") (pin "6") (pinfunction "(OC3B/INT4)PE4_6") (pintype "bidirectional"))
      (node (ref "U8") (pin "3") (pinfunction "SQW/~{INT}_3") (pintype "output"))
    )
    (net (code "104") (name "RXI") (class "Default")
      (node (ref "D1") (pin "C") (pinfunction "C_C") (pintype "passive"))
      (node (ref "J1") (pin "P$3") (pinfunction "RXI_P$3") (pintype "passive"))
      (node (ref "U1") (pin "3") (pinfunction "(TXD0)PE1_3") (pintype "bidirectional"))
      (node (ref "U2") (pin "3") (pinfunction "RXI_3") (pintype "bidirectional"))
    )
    (net (code "105") (name "SCK") (class "Default")
      (node (ref "J2") (pin "3") (pinfunction "3_3") (pintype "passive"))
      (node (ref "U1") (pin "20") (pinfunction "(SCK/PCINT1)PB1_20") (pintype "bidirectional"))
    )
    (net (code "106") (name "SCL") (class "Default")
      (node (ref "R18") (pin "1") (pinfunction "1_1") (pintype "passive"))
      (node (ref "SCL") (pin "TP") (pinfunction "TP_TP") (pintype "input"))
      (node (ref "U1") (pin "43") (pinfunction "(SCL/INT0)PD0_43") (pintype "bidirectional"))
      (node (ref "U8") (pin "16") (pinfunction "SCL_16") (pintype "input"))
    )
    (net (code "107") (name "SDA") (class "Default")
      (node (ref "R17") (pin "1") (pinfunction "1_1") (pintype "passive"))
      (node (ref "SDA") (pin "TP") (pinfunction "TP_TP") (pintype "input"))
      (node (ref "U1") (pin "44") (pinfunction "(SDA/INT1)PD1_44") (pintype "bidirectional"))
      (node (ref "U8") (pin "15") (pinfunction "SDA_15") (pintype "bidirectional"))
    )
    (net (code "108") (name "TIME_MODE") (class "Default")
      (node (ref "S1") (pin "15") (pinfunction "15_15") (pintype "passive"))
      (node (ref "U1") (pin "72") (pinfunction "(AD6)PA6_72") (pintype "bidirectional"))
    )
    (net (code "109") (name "TWO") (class "Default")
      (node (ref "S1") (pin "11") (pinfunction "11_11") (pintype "passive"))
      (node (ref "U1") (pin "76") (pinfunction "(AD2)PA2_76") (pintype "bidirectional"))
    )
    (net (code "110") (name "TXO") (class "Default")
      (node (ref "D2") (pin "C") (pinfunction "C_C") (pintype "passive"))
      (node (ref "J1") (pin "P$2") (pinfunction "TXO_P$2") (pintype "passive"))
      (node (ref "U1") (pin "2") (pinfunction "(RXD0/PCIN8)PE0_2") (pintype "bidirectional"))
      (node (ref "U2") (pin "2") (pinfunction "TXO_2") (pintype "bidirectional"))
    )
    (net (code "111") (name "VCCA") (class "Default")
      (node (ref "5V_ANALOG") (pin "TP") (pinfunction "TP_TP") (pintype "input"))
      (node (ref "PH1") (pin "1") (pinfunction "1_1") (pintype "passive"))
      (node (ref "U1") (pin "100") (pinfunction "AVCC_100") (pintype "power_in"))
      (node (ref "U1") (pin "98") (pinfunction "AREF_98") (pintype "bidirectional"))
      (node (ref "U14") (pin "3") (pinfunction "VO_3") (pintype "passive"))
    )
    (net (code "112") (name "VOUT") (class "Default")
      (node (ref "C13") (pin "1") (pinfunction "1_1") (pintype "passive"))
      (node (ref "C16") (pin "1") (pinfunction "1_1") (pintype "passive"))
      (node (ref "C17") (pin "1") (pinfunction "1_1") (pintype "passive"))
      (node (ref "C18") (pin "1") (pinfunction "1_1") (pintype "passive"))
      (node (ref "T3") (pin "10") (pinfunction "D_10") (pintype "passive"))
      (node (ref "T3") (pin "11") (pinfunction "D_11") (pintype "passive"))
      (node (ref "T3") (pin "12") (pinfunction "D_12") (pintype "passive"))
      (node (ref "T3") (pin "5") (pinfunction "D_5") (pintype "passive"))
      (node (ref "T3") (pin "6") (pinfunction "D_6") (pintype "passive"))
      (node (ref "T3") (pin "7") (pinfunction "D_7") (pintype "passive"))
      (node (ref "T3") (pin "8") (pinfunction "D_8") (pintype "passive"))
      (node (ref "T3") (pin "9") (pinfunction "D_9") (pintype "passive"))
      (node (ref "U12") (pin "16") (pinfunction "VBUS_16") (pintype "bidirectional"))
      (node (ref "U13") (pin "1") (pinfunction "VI_1") (pintype "input"))
      (node (ref "U14") (pin "1") (pinfunction "VI_1") (pintype "input"))
      (node (ref "U7") (pin "1") (pinfunction "VCC_1") (pintype "bidirectional"))
      (node (ref "VOUT") (pin "TP") (pinfunction "TP_TP") (pintype "input"))
    )
    (net (code "113") (name "V_USB") (class "Default")
      (node (ref "C15") (pin "1") (pinfunction "1_1") (pintype "passive"))
      (node (ref "J5") (pin "A4B9") (pinfunction "VBUS_A4B9") (pintype "power_in"))
      (node (ref "J5") (pin "B4A9") (pinfunction "VBUS_B4A9") (pintype "power_in"))
      (node (ref "SJ1") (pin "1") (pinfunction "1_1") (pintype "passive"))
      (node (ref "T3") (pin "1") (pinfunction "S_1") (pintype "passive"))
      (node (ref "T3") (pin "2") (pinfunction "S_2") (pintype "passive"))
      (node (ref "T3") (pin "3") (pinfunction "S_3") (pintype "passive"))
      (node (ref "U12") (pin "2") (pinfunction "VIN_2") (pintype "bidirectional"))
      (node (ref "V_USB") (pin "TP") (pinfunction "TP_TP") (pintype "input"))
    )
    (net (code "114") (name "unconnected-(J5-SBU1-PadA8)") (class "Default")
      (node (ref "J5") (pin "A8") (pinfunction "SBU1_A8") (pintype "bidirectional"))
    )
    (net (code "115") (name "unconnected-(J5-SBU2-PadB8)") (class "Default")
      (node (ref "J5") (pin "B8") (pinfunction "SBU2_B8") (pintype "bidirectional"))
    )
    (net (code "116") (name "unconnected-(U1-(ADC1)PF1-Pad96)") (class "Default")
      (node (ref "U1") (pin "96") (pinfunction "(ADC1)PF1_96") (pintype "bidirectional"))
    )
    (net (code "117") (name "unconnected-(U1-(ADC2)PF2-Pad95)") (class "Default")
      (node (ref "U1") (pin "95") (pinfunction "(ADC2)PF2_95") (pintype "bidirectional"))
    )
    (net (code "118") (name "unconnected-(U1-(ADC3)PF3-Pad94)") (class "Default")
      (node (ref "U1") (pin "94") (pinfunction "(ADC3)PF3_94") (pintype "bidirectional"))
    )
    (net (code "119") (name "unconnected-(U1-(ADC4{slash}TCK)PF4-Pad93)") (class "Default")
      (node (ref "U1") (pin "93") (pinfunction "(ADC4/TCK)PF4_93") (pintype "bidirectional"))
    )
    (net (code "120") (name "unconnected-(U1-(ADC5{slash}TMS)PF5-Pad92)") (class "Default")
      (node (ref "U1") (pin "92") (pinfunction "(ADC5/TMS)PF5_92") (pintype "bidirectional"))
    )
    (net (code "121") (name "unconnected-(U1-(ADC6{slash}TDO)PF6-Pad91)") (class "Default")
      (node (ref "U1") (pin "91") (pinfunction "(ADC6/TDO)PF6_91") (pintype "bidirectional"))
    )
    (net (code "122") (name "unconnected-(U1-(ADC7{slash}TDI)PF7-Pad90)") (class "Default")
      (node (ref "U1") (pin "90") (pinfunction "(ADC7/TDI)PF7_90") (pintype "bidirectional"))
    )
    (net (code "123") (name "unconnected-(U1-(CLKO{slash}ICP3{slash}INT7)PE7-Pad9)") (class "Default")
      (node (ref "U1") (pin "9") (pinfunction "(CLKO/ICP3/INT7)PE7_9") (pintype "bidirectional"))
    )
    (net (code "124") (name "unconnected-(U1-(ICP1)PD4-Pad47)") (class "Default")
      (node (ref "U1") (pin "47") (pinfunction "(ICP1)PD4_47") (pintype "bidirectional"))
    )
    (net (code "125") (name "unconnected-(U1-(OC0A{slash}OC1C{slash}PCINT7)PB7-Pad26)") (class "Default")
      (node (ref "U1") (pin "26") (pinfunction "(OC0A/OC1C/PCINT7)PB7_26") (pintype "bidirectional"))
    )
    (net (code "126") (name "unconnected-(U1-(OC1A{slash}PCINT5)PB5-Pad24)") (class "Default")
      (node (ref "U1") (pin "24") (pinfunction "(OC1A/PCINT5)PB5_24") (pintype "bidirectional"))
    )
    (net (code "127") (name "unconnected-(U1-(OC1B{slash}PCINT6)PB6-Pad25)") (class "Default")
      (node (ref "U1") (pin "25") (pinfunction "(OC1B/PCINT6)PB6_25") (pintype "bidirectional"))
    )
    (net (code "128") (name "unconnected-(U1-(OC2A{slash}PCINT4)PB4-Pad23)") (class "Default")
      (node (ref "U1") (pin "23") (pinfunction "(OC2A/PCINT4)PB4_23") (pintype "bidirectional"))
    )
    (net (code "129") (name "unconnected-(U1-(OC3A{slash}AIN1)PE3-Pad5)") (class "Default")
      (node (ref "U1") (pin "5") (pinfunction "(OC3A/AIN1)PE3_5") (pintype "bidirectional"))
    )
    (net (code "130") (name "unconnected-(U1-(OC3C{slash}INT5)PE5-Pad7)") (class "Default")
      (node (ref "U1") (pin "7") (pinfunction "(OC3C/INT5)PE5_7") (pintype "bidirectional"))
    )
    (net (code "131") (name "unconnected-(U1-(RD)PG1-Pad52)") (class "Default")
      (node (ref "U1") (pin "52") (pinfunction "(RD)PG1_52") (pintype "bidirectional"))
    )
    (net (code "132") (name "unconnected-(U1-(RXD1{slash}INT2)PD2-Pad45)") (class "Default")
      (node (ref "U1") (pin "45") (pinfunction "(RXD1/INT2)PD2_45") (pintype "bidirectional"))
    )
    (net (code "133") (name "unconnected-(U1-(SS{slash}PCINT0)PB0-Pad19)") (class "Default")
      (node (ref "U1") (pin "19") (pinfunction "(SS/PCINT0)PB0_19") (pintype "bidirectional"))
    )
    (net (code "134") (name "unconnected-(U1-(T0)PD7-Pad50)") (class "Default")
      (node (ref "U1") (pin "50") (pinfunction "(T0)PD7_50") (pintype "bidirectional"))
    )
    (net (code "135") (name "unconnected-(U1-(T1)PD6-Pad49)") (class "Default")
      (node (ref "U1") (pin "49") (pinfunction "(T1)PD6_49") (pintype "bidirectional"))
    )
    (net (code "136") (name "unconnected-(U1-(T3{slash}INT6)PE6-Pad8)") (class "Default")
      (node (ref "U1") (pin "8") (pinfunction "(T3/INT6)PE6_8") (pintype "bidirectional"))
    )
    (net (code "137") (name "unconnected-(U1-(TOSC1)PG4-Pad29)") (class "Default")
      (node (ref "U1") (pin "29") (pinfunction "(TOSC1)PG4_29") (pintype "bidirectional"))
    )
    (net (code "138") (name "unconnected-(U1-(TOSC2)PG3-Pad28)") (class "Default")
      (node (ref "U1") (pin "28") (pinfunction "(TOSC2)PG3_28") (pintype "bidirectional"))
    )
    (net (code "139") (name "unconnected-(U1-(TXD1{slash}INT3)PD3-Pad46)") (class "Default")
      (node (ref "U1") (pin "46") (pinfunction "(TXD1/INT3)PD3_46") (pintype "bidirectional"))
    )
    (net (code "140") (name "unconnected-(U1-(WR)PG0-Pad51)") (class "Default")
      (node (ref "U1") (pin "51") (pinfunction "(WR)PG0_51") (pintype "bidirectional"))
    )
    (net (code "141") (name "unconnected-(U1-(XCK0{slash}AIN0)PE2-Pad4)") (class "Default")
      (node (ref "U1") (pin "4") (pinfunction "(XCK0/AIN0)PE2_4") (pintype "bidirectional"))
    )
    (net (code "142") (name "unconnected-(U1-(XCK1)PD5-Pad48)") (class "Default")
      (node (ref "U1") (pin "48") (pinfunction "(XCK1)PD5_48") (pintype "bidirectional"))
    )
    (net (code "143") (name "unconnected-(U1-PH0(RXD2)-Pad12)") (class "Default")
      (node (ref "U1") (pin "12") (pinfunction "PH0(RXD2)_12") (pintype "bidirectional"))
    )
    (net (code "144") (name "unconnected-(U1-PH1(TXD2)-Pad13)") (class "Default")
      (node (ref "U1") (pin "13") (pinfunction "PH1(TXD2)_13") (pintype "bidirectional"))
    )
    (net (code "145") (name "unconnected-(U1-PH2(XCK2)-Pad14)") (class "Default")
      (node (ref "U1") (pin "14") (pinfunction "PH2(XCK2)_14") (pintype "bidirectional"))
    )
    (net (code "146") (name "unconnected-(U1-PH3(OC4A)-Pad15)") (class "Default")
      (node (ref "U1") (pin "15") (pinfunction "PH3(OC4A)_15") (pintype "bidirectional"))
    )
    (net (code "147") (name "unconnected-(U1-PH4(OC4B)-Pad16)") (class "Default")
      (node (ref "U1") (pin "16") (pinfunction "PH4(OC4B)_16") (pintype "bidirectional"))
    )
    (net (code "148") (name "unconnected-(U1-PH5(OC4C)-Pad17)") (class "Default")
      (node (ref "U1") (pin "17") (pinfunction "PH5(OC4C)_17") (pintype "bidirectional"))
    )
    (net (code "149") (name "unconnected-(U1-PH6(OC2B)-Pad18)") (class "Default")
      (node (ref "U1") (pin "18") (pinfunction "PH6(OC2B)_18") (pintype "bidirectional"))
    )
    (net (code "150") (name "unconnected-(U1-PH7(T4)-Pad27)") (class "Default")
      (node (ref "U1") (pin "27") (pinfunction "PH7(T4)_27") (pintype "bidirectional"))
    )
    (net (code "151") (name "unconnected-(U1-PJ2(XCK3{slash}PCINT11)-Pad65)") (class "Default")
      (node (ref "U1") (pin "65") (pinfunction "PJ2(XCK3/PCINT11)_65") (pintype "bidirectional"))
    )
    (net (code "152") (name "unconnected-(U1-PJ3(PCINT12)-Pad66)") (class "Default")
      (node (ref "U1") (pin "66") (pinfunction "PJ3(PCINT12)_66") (pintype "bidirectional"))
    )
    (net (code "153") (name "unconnected-(U1-PJ4(PCINT13)-Pad67)") (class "Default")
      (node (ref "U1") (pin "67") (pinfunction "PJ4(PCINT13)_67") (pintype "bidirectional"))
    )
    (net (code "154") (name "unconnected-(U1-PJ5(PCINT14)-Pad68)") (class "Default")
      (node (ref "U1") (pin "68") (pinfunction "PJ5(PCINT14)_68") (pintype "bidirectional"))
    )
    (net (code "155") (name "unconnected-(U1-PJ6(PCINT15)-Pad69)") (class "Default")
      (node (ref "U1") (pin "69") (pinfunction "PJ6(PCINT15)_69") (pintype "bidirectional"))
    )
    (net (code "156") (name "unconnected-(U1-PJ7-Pad79)") (class "Default")
      (node (ref "U1") (pin "79") (pinfunction "PJ7_79") (pintype "bidirectional"))
    )
    (net (code "157") (name "unconnected-(U1-PK0(ADC8{slash}PCINT16)-Pad89)") (class "Default")
      (node (ref "U1") (pin "89") (pinfunction "PK0(ADC8/PCINT16)_89") (pintype "bidirectional"))
    )
    (net (code "158") (name "unconnected-(U1-PK1(ADC9{slash}PCINT17)-Pad88)") (class "Default")
      (node (ref "U1") (pin "88") (pinfunction "PK1(ADC9/PCINT17)_88") (pintype "bidirectional"))
    )
    (net (code "159") (name "unconnected-(U1-PK2(ADC10{slash}PCINT18)-Pad87)") (class "Default")
      (node (ref "U1") (pin "87") (pinfunction "PK2(ADC10/PCINT18)_87") (pintype "bidirectional"))
    )
    (net (code "160") (name "unconnected-(U1-PK3(ADC11{slash}PCINT19)-Pad86)") (class "Default")
      (node (ref "U1") (pin "86") (pinfunction "PK3(ADC11/PCINT19)_86") (pintype "bidirectional"))
    )
    (net (code "161") (name "unconnected-(U1-PK4(ADC12{slash}PCINT20)-Pad85)") (class "Default")
      (node (ref "U1") (pin "85") (pinfunction "PK4(ADC12/PCINT20)_85") (pintype "bidirectional"))
    )
    (net (code "162") (name "unconnected-(U1-PK5(ADC13{slash}PCINT21)-Pad84)") (class "Default")
      (node (ref "U1") (pin "84") (pinfunction "PK5(ADC13/PCINT21)_84") (pintype "bidirectional"))
    )
    (net (code "163") (name "unconnected-(U1-PK6(ADC14{slash}PCINT22)-Pad83)") (class "Default")
      (node (ref "U1") (pin "83") (pinfunction "PK6(ADC14/PCINT22)_83") (pintype "bidirectional"))
    )
    (net (code "164") (name "unconnected-(U1-PK7(ADC15{slash}PCINT23)-Pad82)") (class "Default")
      (node (ref "U1") (pin "82") (pinfunction "PK7(ADC15/PCINT23)_82") (pintype "bidirectional"))
    )
    (net (code "165") (name "unconnected-(U2-~{CTS}-Pad9)") (class "Default")
      (node (ref "U2") (pin "9") (pinfunction "~{CTS}_9") (pintype "bidirectional"))
    )
    (net (code "166") (name "unconnected-(U2-~{DCD}-Pad12)") (class "Default")
      (node (ref "U2") (pin "12") (pinfunction "~{DCD}_12") (pintype "bidirectional"))
    )
    (net (code "167") (name "unconnected-(U2-~{DSR}-Pad10)") (class "Default")
      (node (ref "U2") (pin "10") (pinfunction "~{DSR}_10") (pintype "bidirectional"))
    )
    (net (code "168") (name "unconnected-(U2-~{RI}-Pad11)") (class "Default")
      (node (ref "U2") (pin "11") (pinfunction "~{RI}_11") (pintype "bidirectional"))
    )
    (net (code "169") (name "unconnected-(U2-~{RTS}-Pad14)") (class "Default")
      (node (ref "U2") (pin "14") (pinfunction "~{RTS}_14") (pintype "bidirectional"))
    )
    (net (code "170") (name "unconnected-(U8-32KHZ-Pad1)") (class "Default")
      (node (ref "U8") (pin "1") (pinfunction "32KHZ_1") (pintype "output"))
    )
    (net (code "171") (name "unconnected-(U8-~{RST}-Pad4)") (class "Default")
      (node (ref "U8") (pin "4") (pinfunction "~{RST}_4") (pintype "input"))
    )
    (net (code "172") (name "unconnected-(U11-1PPS-Pad6)") (class "Default")
      (node (ref "U11") (pin "6") (pinfunction "1PPS_6") (pintype "output"))
    )
    (net (code "173") (name "unconnected-(U11-AADET_N-Pad8)") (class "Default")
      (node (ref "U11") (pin "8") (pinfunction "AADET_N_8") (pintype "bidirectional"))
    )
    (net (code "174") (name "unconnected-(U11-EX_ANT-Pad11)") (class "Default")
      (node (ref "U11") (pin "11") (pinfunction "EX_ANT_11") (pintype "input"))
    )
    (net (code "175") (name "unconnected-(U11-RESET-Pad10)") (class "Default")
      (node (ref "U11") (pin "10") (pinfunction "RESET_10") (pintype "input"))
    )
    (net (code "176") (name "unconnected-(U11-TIMER-Pad7)") (class "Default")
      (node (ref "U11") (pin "7") (pinfunction "TIMER_7") (pintype "output"))
    )
  )
)
